# SCH_GasLeakIntegratedVer3_2026-06-25.net
KiCad netlist of a schematic drawn in EasyEDA
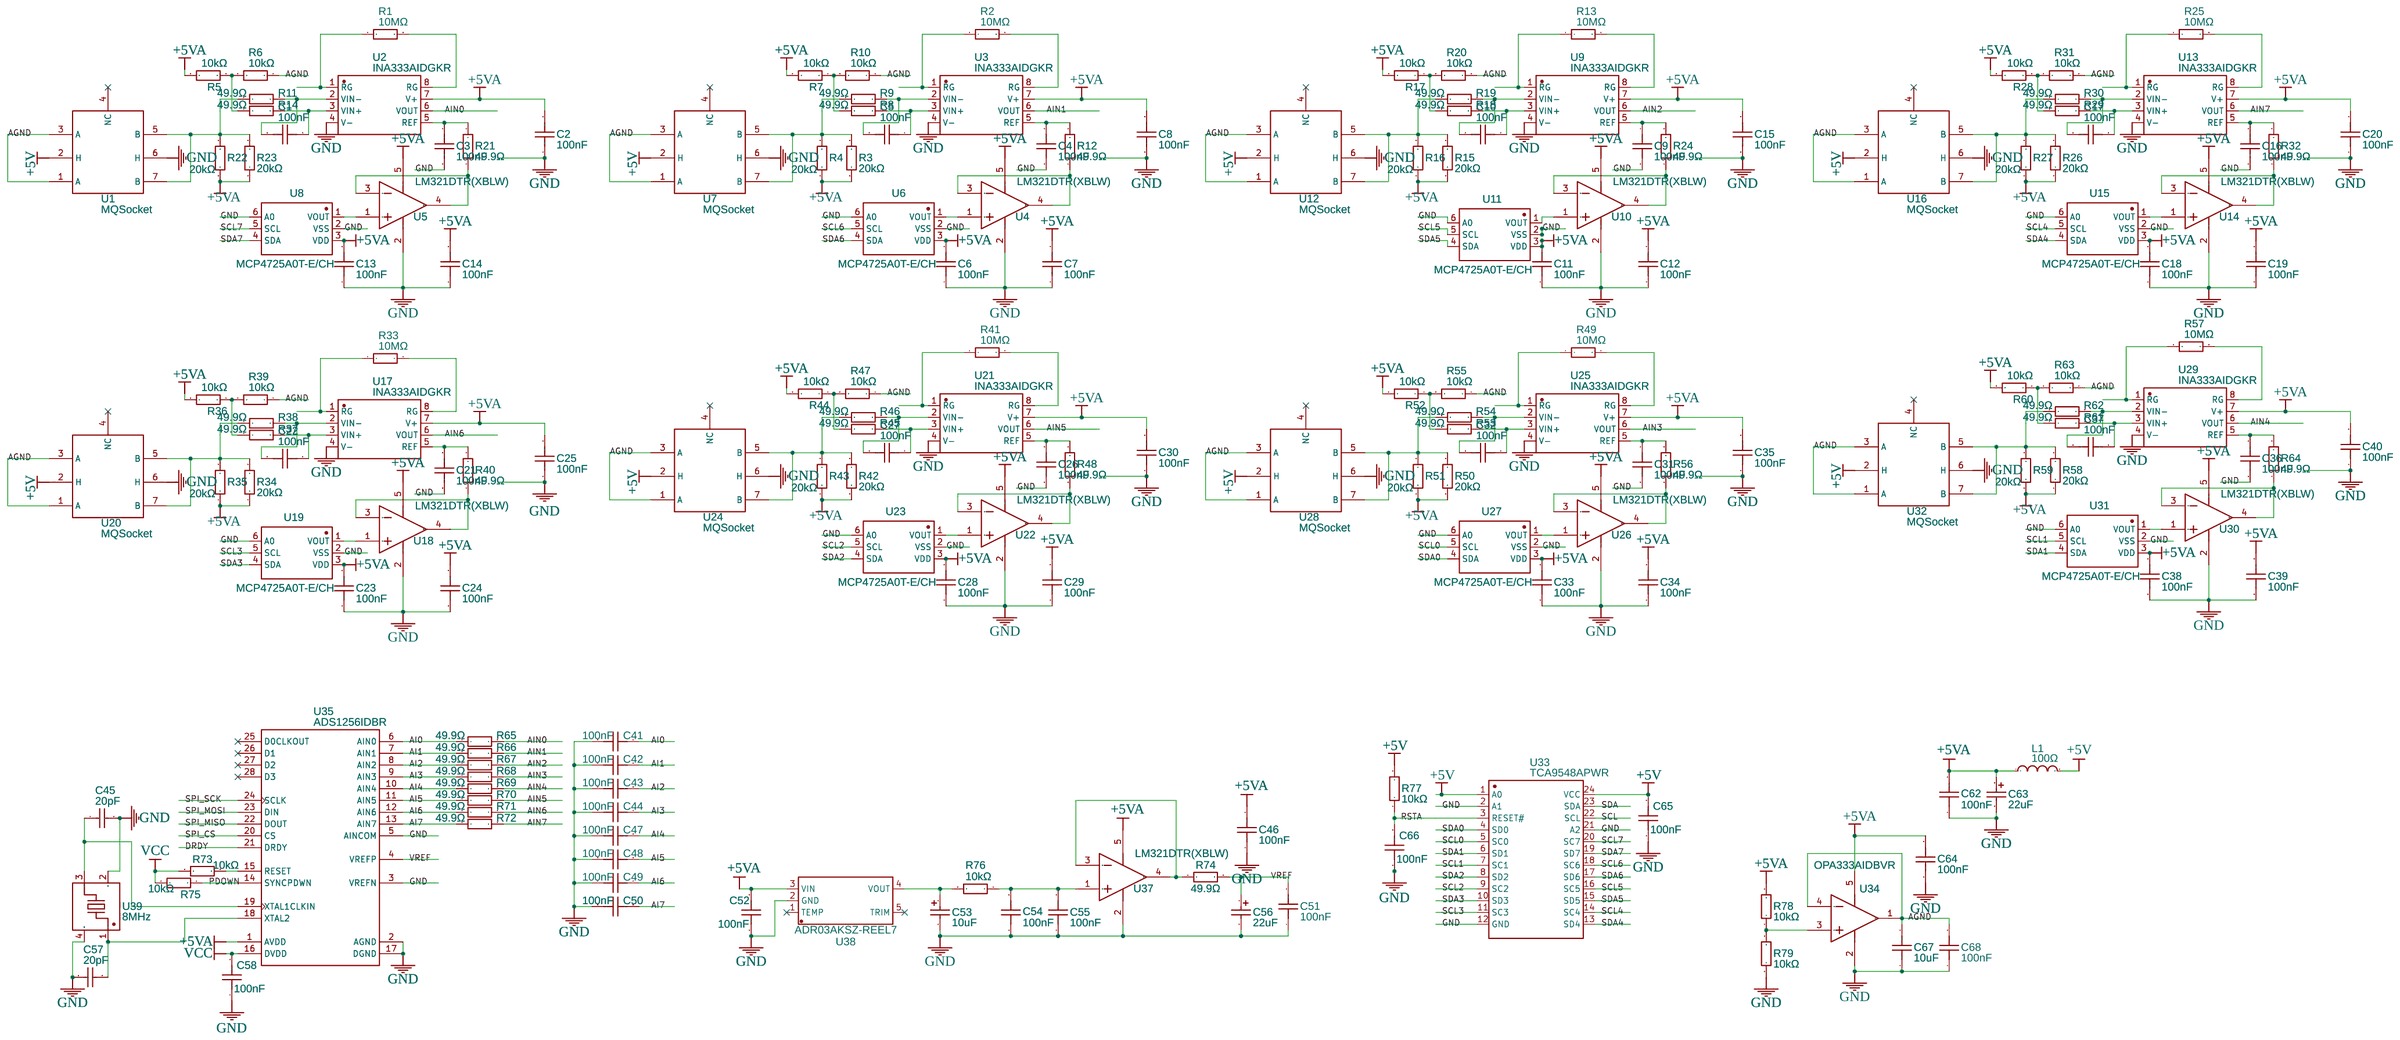
[diagram p0: Sheet_1]
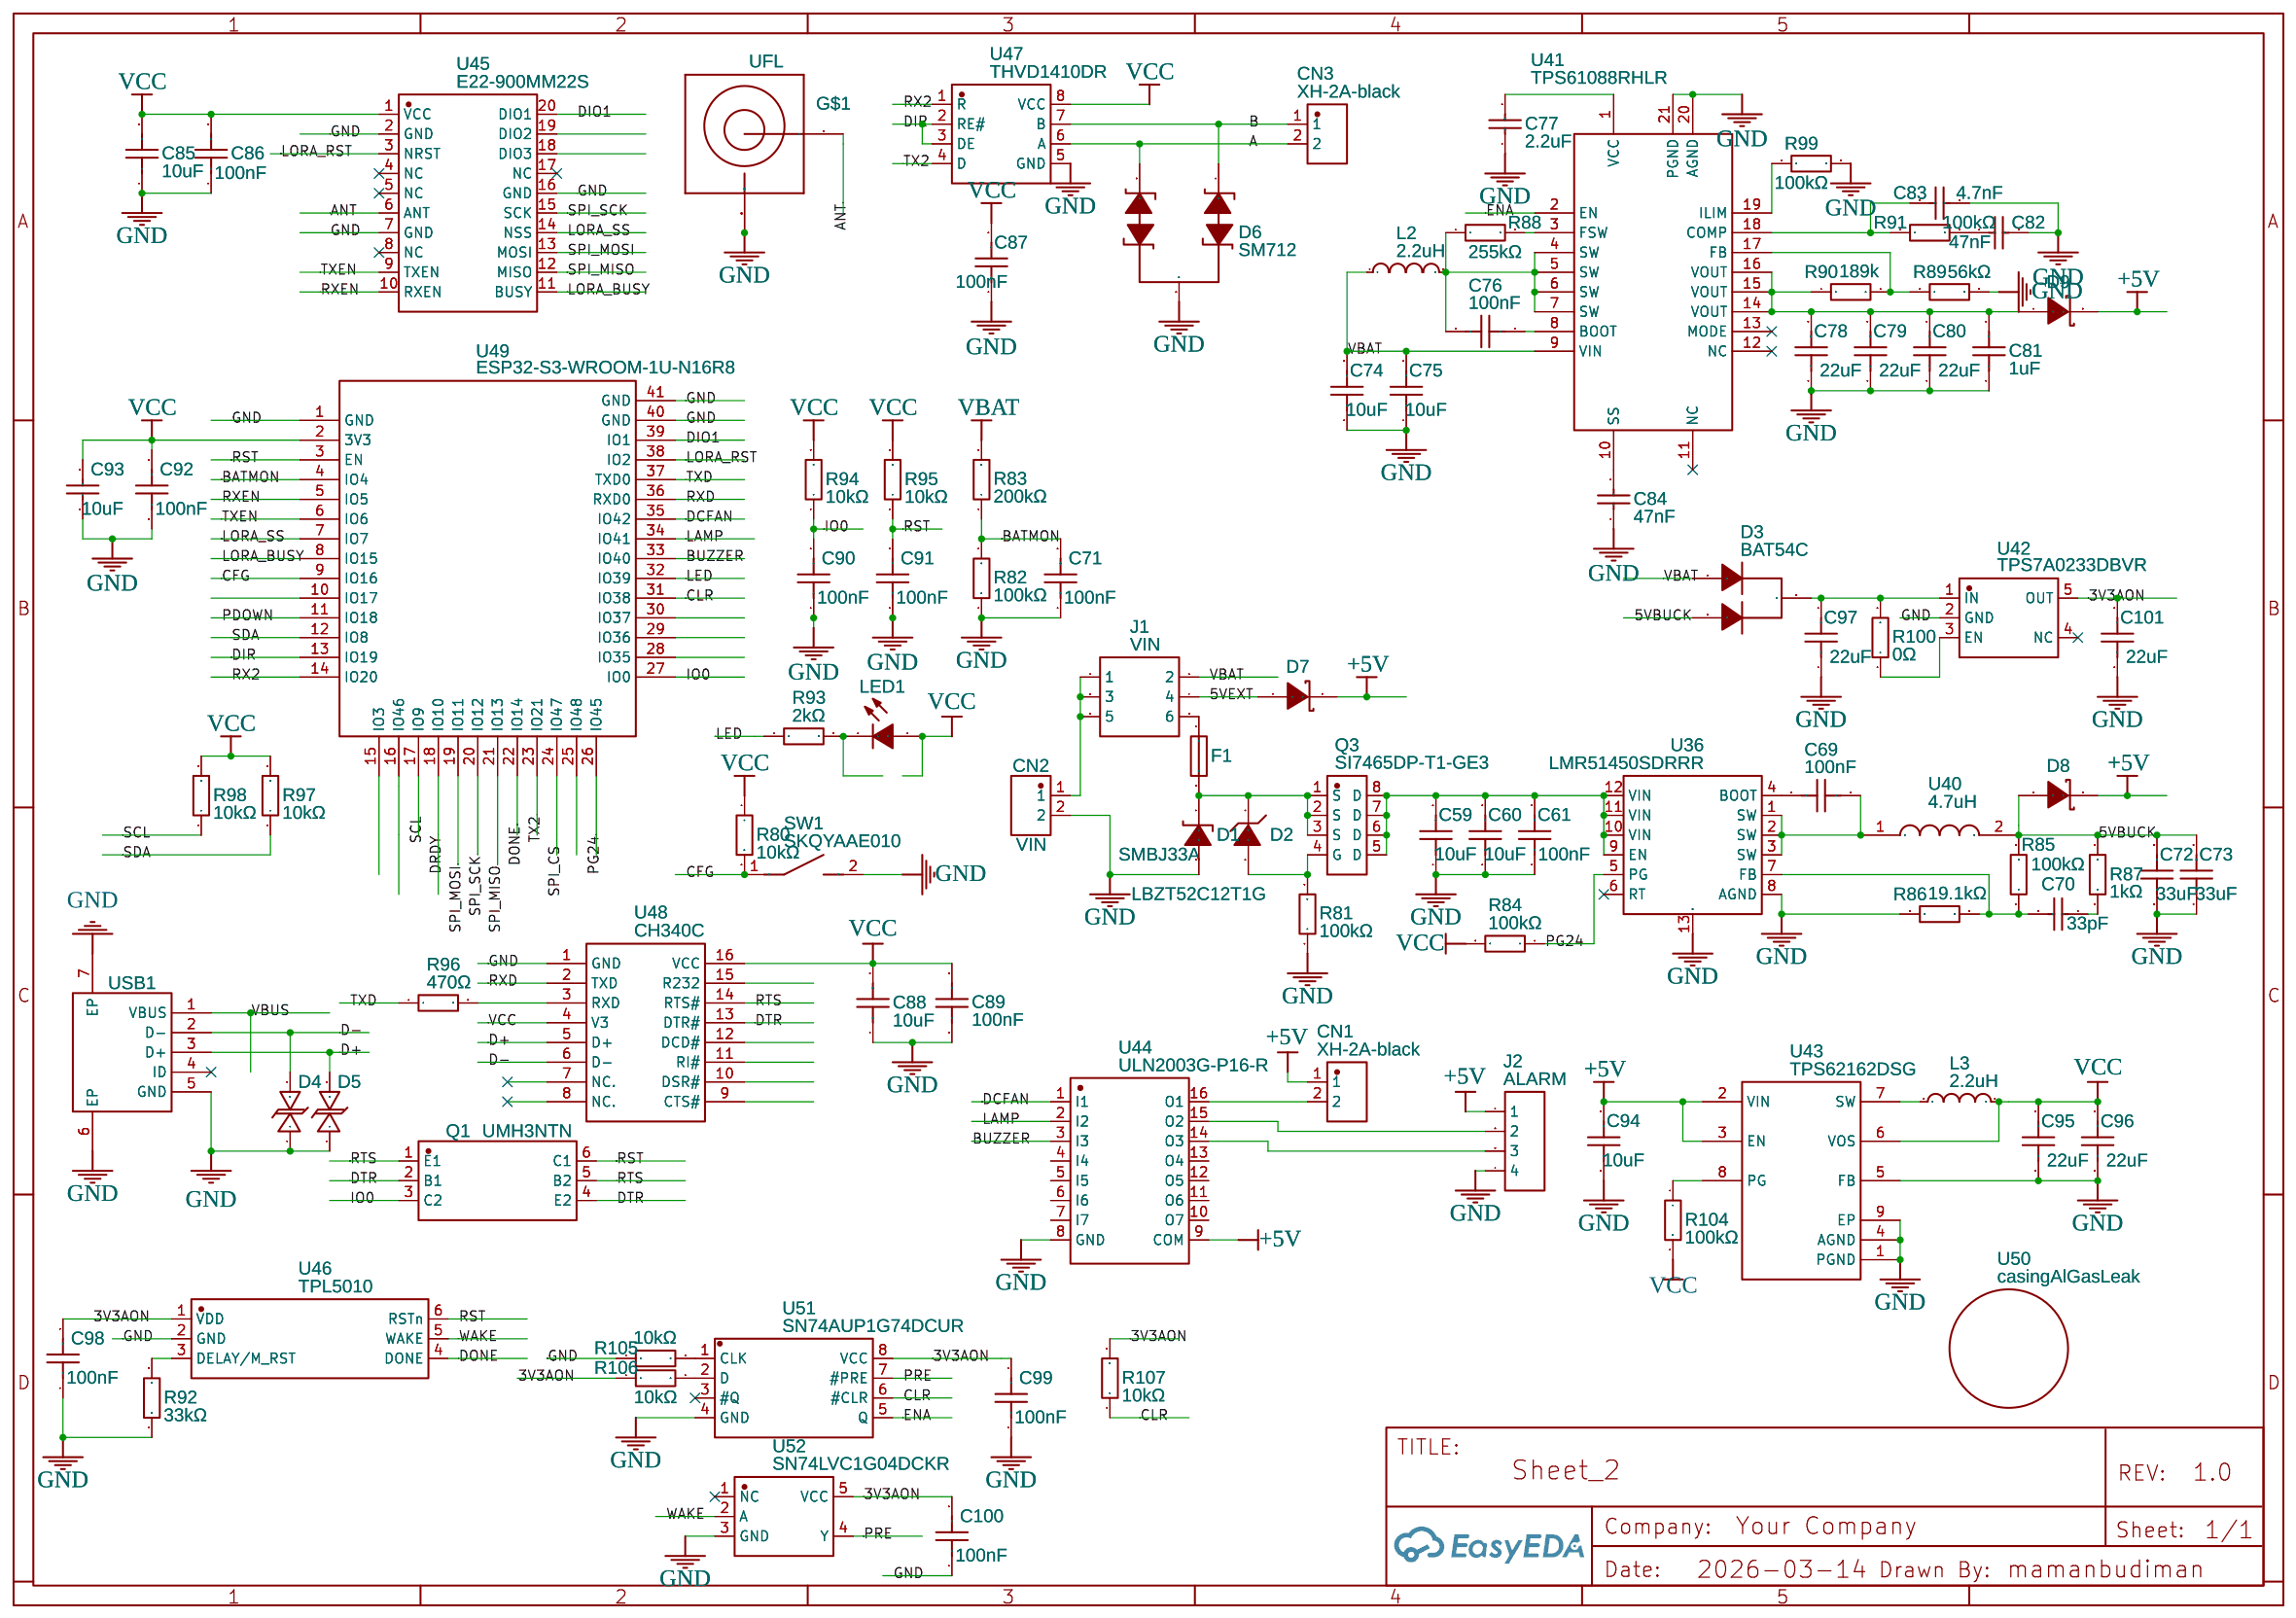
[diagram p1: Sheet_2]

(export (version "E")
  (design (tool "Eeschema 10.0.6"))
  (components
    (comp (ref "C1")
      (value "100nF")
      (fields
        (field (name "Manufacturer Part") "CL05B104KO5NNNC")
        (field (name "Manufacturer") "SAMSUNG(三星)")
      )
      (libsource (lib "") (part "CL05B104KO5NNNC_1"))
    )
    (comp (ref "C2")
      (value "100nF")
      (fields
        (field (name "Manufacturer Part") "CL05B104KO5NNNC")
        (field (name "Manufacturer") "SAMSUNG(三星)")
      )
      (libsource (lib "") (part "CL05B104KO5NNNC"))
    )
    (comp (ref "C3")
      (value "100nF")
      (fields
        (field (name "Manufacturer Part") "CL05B104KO5NNNC")
        (field (name "Manufacturer") "SAMSUNG(三星)")
      )
      (libsource (lib "") (part "CL05B104KO5NNNC_2"))
    )
    (comp (ref "C4")
      (value "100nF")
      (fields
        (field (name "Manufacturer Part") "CL05B104KO5NNNC")
        (field (name "Manufacturer") "SAMSUNG(三星)")
      )
      (libsource (lib "") (part "CL05B104KO5NNNC_2"))
    )
    (comp (ref "C5")
      (value "100nF")
      (fields
        (field (name "Manufacturer Part") "CL05B104KO5NNNC")
        (field (name "Manufacturer") "SAMSUNG(三星)")
      )
      (libsource (lib "") (part "CL05B104KO5NNNC_1"))
    )
    (comp (ref "C6")
      (value "100nF")
      (fields
        (field (name "Manufacturer Part") "CL05B104KO5NNNC")
        (field (name "Manufacturer") "SAMSUNG(三星)")
      )
      (libsource (lib "") (part "CL05B104KO5NNNC"))
    )
    (comp (ref "C7")
      (value "100nF")
      (fields
        (field (name "Manufacturer Part") "CL05B104KO5NNNC")
        (field (name "Manufacturer") "SAMSUNG(三星)")
      )
      (libsource (lib "") (part "CL05B104KO5NNNC"))
    )
    (comp (ref "C8")
      (value "100nF")
      (fields
        (field (name "Manufacturer Part") "CL05B104KO5NNNC")
        (field (name "Manufacturer") "SAMSUNG(三星)")
      )
      (libsource (lib "") (part "CL05B104KO5NNNC"))
    )
    (comp (ref "C9")
      (value "100nF")
      (fields
        (field (name "Manufacturer Part") "CL05B104KO5NNNC")
        (field (name "Manufacturer") "SAMSUNG(三星)")
      )
      (libsource (lib "") (part "CL05B104KO5NNNC_2"))
    )
    (comp (ref "C10")
      (value "100nF")
      (fields
        (field (name "Manufacturer Part") "CL05B104KO5NNNC")
        (field (name "Manufacturer") "SAMSUNG(三星)")
      )
      (libsource (lib "") (part "CL05B104KO5NNNC_1"))
    )
    (comp (ref "C11")
      (value "100nF")
      (fields
        (field (name "Manufacturer Part") "CL05B104KO5NNNC")
        (field (name "Manufacturer") "SAMSUNG(三星)")
      )
      (libsource (lib "") (part "CL05B104KO5NNNC"))
    )
    (comp (ref "C12")
      (value "100nF")
      (fields
        (field (name "Manufacturer Part") "CL05B104KO5NNNC")
        (field (name "Manufacturer") "SAMSUNG(三星)")
      )
      (libsource (lib "") (part "CL05B104KO5NNNC"))
    )
    (comp (ref "C13")
      (value "100nF")
      (fields
        (field (name "Manufacturer Part") "CL05B104KO5NNNC")
        (field (name "Manufacturer") "SAMSUNG(三星)")
      )
      (libsource (lib "") (part "CL05B104KO5NNNC"))
    )
    (comp (ref "C14")
      (value "100nF")
      (fields
        (field (name "Manufacturer Part") "CL05B104KO5NNNC")
        (field (name "Manufacturer") "SAMSUNG(三星)")
      )
      (libsource (lib "") (part "CL05B104KO5NNNC"))
    )
    (comp (ref "C15")
      (value "100nF")
      (fields
        (field (name "Manufacturer Part") "CL05B104KO5NNNC")
        (field (name "Manufacturer") "SAMSUNG(三星)")
      )
      (libsource (lib "") (part "CL05B104KO5NNNC"))
    )
    (comp (ref "C16")
      (value "100nF")
      (fields
        (field (name "Manufacturer Part") "CL05B104KO5NNNC")
        (field (name "Manufacturer") "SAMSUNG(三星)")
      )
      (libsource (lib "") (part "CL05B104KO5NNNC_2"))
    )
    (comp (ref "C17")
      (value "100nF")
      (fields
        (field (name "Manufacturer Part") "CL05B104KO5NNNC")
        (field (name "Manufacturer") "SAMSUNG(三星)")
      )
      (libsource (lib "") (part "CL05B104KO5NNNC_1"))
    )
    (comp (ref "C18")
      (value "100nF")
      (fields
        (field (name "Manufacturer Part") "CL05B104KO5NNNC")
        (field (name "Manufacturer") "SAMSUNG(三星)")
      )
      (libsource (lib "") (part "CL05B104KO5NNNC"))
    )
    (comp (ref "C19")
      (value "100nF")
      (fields
        (field (name "Manufacturer Part") "CL05B104KO5NNNC")
        (field (name "Manufacturer") "SAMSUNG(三星)")
      )
      (libsource (lib "") (part "CL05B104KO5NNNC"))
    )
    (comp (ref "C20")
      (value "100nF")
      (fields
        (field (name "Manufacturer Part") "CL05B104KO5NNNC")
        (field (name "Manufacturer") "SAMSUNG(三星)")
      )
      (libsource (lib "") (part "CL05B104KO5NNNC"))
    )
    (comp (ref "C21")
      (value "100nF")
      (fields
        (field (name "Manufacturer Part") "CL05B104KO5NNNC")
        (field (name "Manufacturer") "SAMSUNG(三星)")
      )
      (libsource (lib "") (part "CL05B104KO5NNNC_2"))
    )
    (comp (ref "C22")
      (value "100nF")
      (fields
        (field (name "Manufacturer Part") "CL05B104KO5NNNC")
        (field (name "Manufacturer") "SAMSUNG(三星)")
      )
      (libsource (lib "") (part "CL05B104KO5NNNC_1"))
    )
    (comp (ref "C23")
      (value "100nF")
      (fields
        (field (name "Manufacturer Part") "CL05B104KO5NNNC")
        (field (name "Manufacturer") "SAMSUNG(三星)")
      )
      (libsource (lib "") (part "CL05B104KO5NNNC"))
    )
    (comp (ref "C24")
      (value "100nF")
      (fields
        (field (name "Manufacturer Part") "CL05B104KO5NNNC")
        (field (name "Manufacturer") "SAMSUNG(三星)")
      )
      (libsource (lib "") (part "CL05B104KO5NNNC"))
    )
    (comp (ref "C25")
      (value "100nF")
      (fields
        (field (name "Manufacturer Part") "CL05B104KO5NNNC")
        (field (name "Manufacturer") "SAMSUNG(三星)")
      )
      (libsource (lib "") (part "CL05B104KO5NNNC"))
    )
    (comp (ref "C26")
      (value "100nF")
      (fields
        (field (name "Manufacturer Part") "CL05B104KO5NNNC")
        (field (name "Manufacturer") "SAMSUNG(三星)")
      )
      (libsource (lib "") (part "CL05B104KO5NNNC_2"))
    )
    (comp (ref "C27")
      (value "100nF")
      (fields
        (field (name "Manufacturer Part") "CL05B104KO5NNNC")
        (field (name "Manufacturer") "SAMSUNG(三星)")
      )
      (libsource (lib "") (part "CL05B104KO5NNNC_1"))
    )
    (comp (ref "C28")
      (value "100nF")
      (fields
        (field (name "Manufacturer Part") "CL05B104KO5NNNC")
        (field (name "Manufacturer") "SAMSUNG(三星)")
      )
      (libsource (lib "") (part "CL05B104KO5NNNC"))
    )
    (comp (ref "C29")
      (value "100nF")
      (fields
        (field (name "Manufacturer Part") "CL05B104KO5NNNC")
        (field (name "Manufacturer") "SAMSUNG(三星)")
      )
      (libsource (lib "") (part "CL05B104KO5NNNC"))
    )
    (comp (ref "C30")
      (value "100nF")
      (fields
        (field (name "Manufacturer Part") "CL05B104KO5NNNC")
        (field (name "Manufacturer") "SAMSUNG(三星)")
      )
      (libsource (lib "") (part "CL05B104KO5NNNC"))
    )
    (comp (ref "C31")
      (value "100nF")
      (fields
        (field (name "Manufacturer Part") "CL05B104KO5NNNC")
        (field (name "Manufacturer") "SAMSUNG(三星)")
      )
      (libsource (lib "") (part "CL05B104KO5NNNC_2"))
    )
    (comp (ref "C32")
      (value "100nF")
      (fields
        (field (name "Manufacturer Part") "CL05B104KO5NNNC")
        (field (name "Manufacturer") "SAMSUNG(三星)")
      )
      (libsource (lib "") (part "CL05B104KO5NNNC_1"))
    )
    (comp (ref "C33")
      (value "100nF")
      (fields
        (field (name "Manufacturer Part") "CL05B104KO5NNNC")
        (field (name "Manufacturer") "SAMSUNG(三星)")
      )
      (libsource (lib "") (part "CL05B104KO5NNNC"))
    )
    (comp (ref "C34")
      (value "100nF")
      (fields
        (field (name "Manufacturer Part") "CL05B104KO5NNNC")
        (field (name "Manufacturer") "SAMSUNG(三星)")
      )
      (libsource (lib "") (part "CL05B104KO5NNNC"))
    )
    (comp (ref "C35")
      (value "100nF")
      (fields
        (field (name "Manufacturer Part") "CL05B104KO5NNNC")
        (field (name "Manufacturer") "SAMSUNG(三星)")
      )
      (libsource (lib "") (part "CL05B104KO5NNNC"))
    )
    (comp (ref "C36")
      (value "100nF")
      (fields
        (field (name "Manufacturer Part") "CL05B104KO5NNNC")
        (field (name "Manufacturer") "SAMSUNG(三星)")
      )
      (libsource (lib "") (part "CL05B104KO5NNNC_2"))
    )
    (comp (ref "C37")
      (value "100nF")
      (fields
        (field (name "Manufacturer Part") "CL05B104KO5NNNC")
        (field (name "Manufacturer") "SAMSUNG(三星)")
      )
      (libsource (lib "") (part "CL05B104KO5NNNC_1"))
    )
    (comp (ref "C38")
      (value "100nF")
      (fields
        (field (name "Manufacturer Part") "CL05B104KO5NNNC")
        (field (name "Manufacturer") "SAMSUNG(三星)")
      )
      (libsource (lib "") (part "CL05B104KO5NNNC"))
    )
    (comp (ref "C39")
      (value "100nF")
      (fields
        (field (name "Manufacturer Part") "CL05B104KO5NNNC")
        (field (name "Manufacturer") "SAMSUNG(三星)")
      )
      (libsource (lib "") (part "CL05B104KO5NNNC"))
    )
    (comp (ref "C40")
      (value "100nF")
      (fields
        (field (name "Manufacturer Part") "CL05B104KO5NNNC")
        (field (name "Manufacturer") "SAMSUNG(三星)")
      )
      (libsource (lib "") (part "CL05B104KO5NNNC"))
    )
    (comp (ref "C41")
      (value "100nF")
      (fields
        (field (name "Manufacturer Part") "CL05B104KO5NNNC")
        (field (name "Manufacturer") "SAMSUNG(三星)")
      )
      (libsource (lib "") (part "CL05B104KO5NNNC_3"))
    )
    (comp (ref "C42")
      (value "100nF")
      (fields
        (field (name "Manufacturer Part") "CL05B104KO5NNNC")
        (field (name "Manufacturer") "SAMSUNG(三星)")
      )
      (libsource (lib "") (part "CL05B104KO5NNNC_3"))
    )
    (comp (ref "C43")
      (value "100nF")
      (fields
        (field (name "Manufacturer Part") "CL05B104KO5NNNC")
        (field (name "Manufacturer") "SAMSUNG(三星)")
      )
      (libsource (lib "") (part "CL05B104KO5NNNC_3"))
    )
    (comp (ref "C44")
      (value "100nF")
      (fields
        (field (name "Manufacturer Part") "CL05B104KO5NNNC")
        (field (name "Manufacturer") "SAMSUNG(三星)")
      )
      (libsource (lib "") (part "CL05B104KO5NNNC_3"))
    )
    (comp (ref "C45")
      (value "20pF")
      (fields (field (name "Manufacturer Part") "0402CG200J500NT") (field (name "Manufacturer") "FH(风华)"))
      (libsource (lib "") (part "0402CG200J500NT"))
    )
    (comp (ref "C46")
      (value "100nF")
      (fields
        (field (name "Manufacturer Part") "CL05B104KO5NNNC")
        (field (name "Manufacturer") "SAMSUNG(三星)")
      )
      (libsource (lib "") (part "CL05B104KO5NNNC"))
    )
    (comp (ref "C47")
      (value "100nF")
      (fields
        (field (name "Manufacturer Part") "CL05B104KO5NNNC")
        (field (name "Manufacturer") "SAMSUNG(三星)")
      )
      (libsource (lib "") (part "CL05B104KO5NNNC_3"))
    )
    (comp (ref "C48")
      (value "100nF")
      (fields
        (field (name "Manufacturer Part") "CL05B104KO5NNNC")
        (field (name "Manufacturer") "SAMSUNG(三星)")
      )
      (libsource (lib "") (part "CL05B104KO5NNNC_3"))
    )
    (comp (ref "C49")
      (value "100nF")
      (fields
        (field (name "Manufacturer Part") "CL05B104KO5NNNC")
        (field (name "Manufacturer") "SAMSUNG(三星)")
      )
      (libsource (lib "") (part "CL05B104KO5NNNC_3"))
    )
    (comp (ref "C50")
      (value "100nF")
      (fields
        (field (name "Manufacturer Part") "CL05B104KO5NNNC")
        (field (name "Manufacturer") "SAMSUNG(三星)")
      )
      (libsource (lib "") (part "CL05B104KO5NNNC_3"))
    )
    (comp (ref "C51")
      (value "100nF")
      (fields
        (field (name "Manufacturer Part") "CL05B104KO5NNNC")
        (field (name "Manufacturer") "SAMSUNG(三星)")
      )
      (libsource (lib "") (part "CL05B104KO5NNNC"))
    )
    (comp (ref "C52")
      (value "100nF")
      (fields
        (field (name "Manufacturer Part") "CL05B104KO5NNNC")
        (field (name "Manufacturer") "SAMSUNG(三星)")
      )
      (libsource (lib "") (part "CL05B104KO5NNNC"))
    )
    (comp (ref "C53")
      (value "10uF")
      (fields (field (name "Manufacturer Part") "TAJA106K016RNJ") (field (name "Manufacturer") "Kyocera AVX"))
      (libsource (lib "") (part "TAJA106K016RNJ"))
    )
    (comp (ref "C54")
      (value "100nF")
      (fields
        (field (name "Manufacturer Part") "CL05B104KO5NNNC")
        (field (name "Manufacturer") "SAMSUNG(三星)")
      )
      (libsource (lib "") (part "CL05B104KO5NNNC"))
    )
    (comp (ref "C55")
      (value "100nF")
      (fields
        (field (name "Manufacturer Part") "CL05B104KO5NNNC")
        (field (name "Manufacturer") "SAMSUNG(三星)")
      )
      (libsource (lib "") (part "CL05B104KO5NNNC"))
    )
    (comp (ref "C56")
      (value "22uF")
      (fields (field (name "Manufacturer Part") "TAJA226M010RNJ") (field (name "Manufacturer") "Kyocera AVX"))
      (libsource (lib "") (part "TAJA226M010RNJ"))
    )
    (comp (ref "C57")
      (value "20pF")
      (fields (field (name "Manufacturer Part") "0402CG200J500NT") (field (name "Manufacturer") "FH(风华)"))
      (libsource (lib "") (part "0402CG200J500NT"))
    )
    (comp (ref "C58")
      (value "100nF")
      (fields (field (name "Manufacturer Part") "CC0603KRX7R9BB104") (field (name "Manufacturer") "YAGEO"))
      (libsource (lib "") (part "CC0603KRX7R9BB104"))
    )
    (comp (ref "C62")
      (value "100nF")
      (fields
        (field (name "Manufacturer Part") "CL05B104KO5NNNC")
        (field (name "Manufacturer") "SAMSUNG(三星)")
      )
      (libsource (lib "") (part "CL05B104KO5NNNC"))
    )
    (comp (ref "C63")
      (value "22uF")
      (fields (field (name "Manufacturer Part") "TAJA226M010RNJ") (field (name "Manufacturer") "Kyocera AVX"))
      (libsource (lib "") (part "TAJA226M010RNJ"))
    )
    (comp (ref "C64")
      (value "100nF")
      (fields
        (field (name "Manufacturer Part") "CC0603KRX7R9BB104")
        (field (name "Manufacturer") "YAGEO(国巨)")
      )
      (libsource (lib "") (part "CC0603KRX7R9BB104"))
    )
    (comp (ref "C65")
      (value "100nF")
      (fields (field (name "Manufacturer Part") "CC0603KRX7R9BB104") (field (name "Manufacturer") "YAGEO"))
      (libsource (lib "") (part "CC0603KRX7R9BB104"))
    )
    (comp (ref "C66")
      (value "100nF")
      (fields (field (name "Manufacturer Part") "CC0603KRX7R9BB104") (field (name "Manufacturer") "YAGEO"))
      (libsource (lib "") (part "CC0603KRX7R9BB104"))
    )
    (comp (ref "C67")
      (value "10uF")
      (fields
        (field (name "Manufacturer Part") "CL10A106KP8NNNC")
        (field (name "Manufacturer") "SAMSUNG(三星)")
      )
      (libsource (lib "") (part "CL10A106KP8NNNC"))
    )
    (comp (ref "C68")
      (value "100nF")
      (fields
        (field (name "Manufacturer Part") "CC0603KRX7R9BB104")
        (field (name "Manufacturer") "YAGEO(国巨)")
      )
      (libsource (lib "") (part "CC0603KRX7R9BB104"))
    )
    (comp (ref "L1")
      (value "100Ω")
      (fields (field (name "Manufacturer Part") "GZ2012D101TF") (field (name "Manufacturer") "Sunlord(顺络)"))
      (libsource (lib "") (part "GZ2012D101TF"))
    )
    (comp (ref "R1")
      (value "10MΩ")
      (fields
        (field (name "Manufacturer Part") "0603WAF1005T5E")
        (field (name "Manufacturer") "UNI-ROYAL(厚声)")
      )
      (libsource (lib "") (part "0603WAF1005T5E"))
    )
    (comp (ref "R2")
      (value "10MΩ")
      (fields
        (field (name "Manufacturer Part") "0603WAF1005T5E")
        (field (name "Manufacturer") "UNI-ROYAL(厚声)")
      )
      (libsource (lib "") (part "0603WAF1005T5E"))
    )
    (comp (ref "R3")
      (value "20kΩ")
      (fields
        (field (name "Manufacturer Part") "0603WAF2002T5E")
        (field (name "Manufacturer") "UNI-ROYAL(厚声)")
      )
      (libsource (lib "") (part "0603WAF2002T5E"))
    )
    (comp (ref "R4")
      (value "20kΩ")
      (fields
        (field (name "Manufacturer Part") "0603WAF2002T5E")
        (field (name "Manufacturer") "UNI-ROYAL(厚声)")
      )
      (libsource (lib "") (part "0603WAF2002T5E"))
    )
    (comp (ref "R5")
      (value "10kΩ")
      (fields (field (name "Manufacturer Part") "RT0603BRD0710KL") (field (name "Manufacturer") "YAGEO(国巨)"))
      (libsource (lib "") (part "RT0603BRD0710KL"))
    )
    (comp (ref "R6")
      (value "10kΩ")
      (fields (field (name "Manufacturer Part") "RT0603BRD0710KL") (field (name "Manufacturer") "YAGEO(国巨)"))
      (libsource (lib "") (part "RT0603BRD0710KL"))
    )
    (comp (ref "R7")
      (value "10kΩ")
      (fields (field (name "Manufacturer Part") "RT0603BRD0710KL") (field (name "Manufacturer") "YAGEO(国巨)"))
      (libsource (lib "") (part "RT0603BRD0710KL"))
    )
    (comp (ref "R8")
      (value "49.9Ω")
      (fields (field (name "Manufacturer Part") "RC-02K49R9FT") (field (name "Manufacturer") "FH(风华)"))
      (libsource (lib "") (part "RC-02K49R9FT"))
    )
    (comp (ref "R9")
      (value "49.9Ω")
      (fields (field (name "Manufacturer Part") "RC-02K49R9FT") (field (name "Manufacturer") "FH(风华)"))
      (libsource (lib "") (part "RC-02K49R9FT"))
    )
    (comp (ref "R10")
      (value "10kΩ")
      (fields (field (name "Manufacturer Part") "RT0603BRD0710KL") (field (name "Manufacturer") "YAGEO(国巨)"))
      (libsource (lib "") (part "RT0603BRD0710KL"))
    )
    (comp (ref "R11")
      (value "49.9Ω")
      (fields (field (name "Manufacturer Part") "RC-02K49R9FT") (field (name "Manufacturer") "FH(风华)"))
      (libsource (lib "") (part "RC-02K49R9FT"))
    )
    (comp (ref "R12")
      (value "49.9Ω")
      (fields (field (name "Manufacturer Part") "RC-02K49R9FT") (field (name "Manufacturer") "FH(风华)"))
      (libsource (lib "") (part "RC-02K49R9FT_1"))
    )
    (comp (ref "R13")
      (value "10MΩ")
      (fields
        (field (name "Manufacturer Part") "0603WAF1005T5E")
        (field (name "Manufacturer") "UNI-ROYAL(厚声)")
      )
      (libsource (lib "") (part "0603WAF1005T5E"))
    )
    (comp (ref "R14")
      (value "49.9Ω")
      (fields (field (name "Manufacturer Part") "RC-02K49R9FT") (field (name "Manufacturer") "FH(风华)"))
      (libsource (lib "") (part "RC-02K49R9FT"))
    )
    (comp (ref "R15")
      (value "20kΩ")
      (fields
        (field (name "Manufacturer Part") "0603WAF2002T5E")
        (field (name "Manufacturer") "UNI-ROYAL(厚声)")
      )
      (libsource (lib "") (part "0603WAF2002T5E"))
    )
    (comp (ref "R16")
      (value "20kΩ")
      (fields
        (field (name "Manufacturer Part") "0603WAF2002T5E")
        (field (name "Manufacturer") "UNI-ROYAL(厚声)")
      )
      (libsource (lib "") (part "0603WAF2002T5E"))
    )
    (comp (ref "R17")
      (value "10kΩ")
      (fields (field (name "Manufacturer Part") "RT0603BRD0710KL") (field (name "Manufacturer") "YAGEO(国巨)"))
      (libsource (lib "") (part "RT0603BRD0710KL"))
    )
    (comp (ref "R18")
      (value "49.9Ω")
      (fields (field (name "Manufacturer Part") "RC-02K49R9FT") (field (name "Manufacturer") "FH(风华)"))
      (libsource (lib "") (part "RC-02K49R9FT"))
    )
    (comp (ref "R19")
      (value "49.9Ω")
      (fields (field (name "Manufacturer Part") "RC-02K49R9FT") (field (name "Manufacturer") "FH(风华)"))
      (libsource (lib "") (part "RC-02K49R9FT"))
    )
    (comp (ref "R20")
      (value "10kΩ")
      (fields (field (name "Manufacturer Part") "RT0603BRD0710KL") (field (name "Manufacturer") "YAGEO(国巨)"))
      (libsource (lib "") (part "RT0603BRD0710KL"))
    )
    (comp (ref "R21")
      (value "49.9Ω")
      (fields (field (name "Manufacturer Part") "RC-02K49R9FT") (field (name "Manufacturer") "FH(风华)"))
      (libsource (lib "") (part "RC-02K49R9FT_1"))
    )
    (comp (ref "R22")
      (value "20kΩ")
      (fields
        (field (name "Manufacturer Part") "0603WAF2002T5E")
        (field (name "Manufacturer") "UNI-ROYAL(厚声)")
      )
      (libsource (lib "") (part "0603WAF2002T5E"))
    )
    (comp (ref "R23")
      (value "20kΩ")
      (fields
        (field (name "Manufacturer Part") "0603WAF2002T5E")
        (field (name "Manufacturer") "UNI-ROYAL(厚声)")
      )
      (libsource (lib "") (part "0603WAF2002T5E"))
    )
    (comp (ref "R24")
      (value "49.9Ω")
      (fields (field (name "Manufacturer Part") "RC-02K49R9FT") (field (name "Manufacturer") "FH(风华)"))
      (libsource (lib "") (part "RC-02K49R9FT_1"))
    )
    (comp (ref "R25")
      (value "10MΩ")
      (fields
        (field (name "Manufacturer Part") "0603WAF1005T5E")
        (field (name "Manufacturer") "UNI-ROYAL(厚声)")
      )
      (libsource (lib "") (part "0603WAF1005T5E"))
    )
    (comp (ref "R26")
      (value "20kΩ")
      (fields
        (field (name "Manufacturer Part") "0603WAF2002T5E")
        (field (name "Manufacturer") "UNI-ROYAL(厚声)")
      )
      (libsource (lib "") (part "0603WAF2002T5E"))
    )
    (comp (ref "R27")
      (value "20kΩ")
      (fields
        (field (name "Manufacturer Part") "0603WAF2002T5E")
        (field (name "Manufacturer") "UNI-ROYAL(厚声)")
      )
      (libsource (lib "") (part "0603WAF2002T5E"))
    )
    (comp (ref "R28")
      (value "10kΩ")
      (fields (field (name "Manufacturer Part") "RT0603BRD0710KL") (field (name "Manufacturer") "YAGEO(国巨)"))
      (libsource (lib "") (part "RT0603BRD0710KL"))
    )
    (comp (ref "R29")
      (value "49.9Ω")
      (fields (field (name "Manufacturer Part") "RC-02K49R9FT") (field (name "Manufacturer") "FH(风华)"))
      (libsource (lib "") (part "RC-02K49R9FT"))
    )
    (comp (ref "R30")
      (value "49.9Ω")
      (fields (field (name "Manufacturer Part") "RC-02K49R9FT") (field (name "Manufacturer") "FH(风华)"))
      (libsource (lib "") (part "RC-02K49R9FT"))
    )
    (comp (ref "R31")
      (value "10kΩ")
      (fields (field (name "Manufacturer Part") "RT0603BRD0710KL") (field (name "Manufacturer") "YAGEO(国巨)"))
      (libsource (lib "") (part "RT0603BRD0710KL"))
    )
    (comp (ref "R32")
      (value "49.9Ω")
      (fields (field (name "Manufacturer Part") "RC-02K49R9FT") (field (name "Manufacturer") "FH(风华)"))
      (libsource (lib "") (part "RC-02K49R9FT_1"))
    )
    (comp (ref "R33")
      (value "10MΩ")
      (fields
        (field (name "Manufacturer Part") "0603WAF1005T5E")
        (field (name "Manufacturer") "UNI-ROYAL(厚声)")
      )
      (libsource (lib "") (part "0603WAF1005T5E"))
    )
    (comp (ref "R34")
      (value "20kΩ")
      (fields
        (field (name "Manufacturer Part") "0603WAF2002T5E")
        (field (name "Manufacturer") "UNI-ROYAL(厚声)")
      )
      (libsource (lib "") (part "0603WAF2002T5E"))
    )
    (comp (ref "R35")
      (value "20kΩ")
      (fields
        (field (name "Manufacturer Part") "0603WAF2002T5E")
        (field (name "Manufacturer") "UNI-ROYAL(厚声)")
      )
      (libsource (lib "") (part "0603WAF2002T5E"))
    )
    (comp (ref "R36")
      (value "10kΩ")
      (fields (field (name "Manufacturer Part") "RT0603BRD0710KL") (field (name "Manufacturer") "YAGEO(国巨)"))
      (libsource (lib "") (part "RT0603BRD0710KL"))
    )
    (comp (ref "R37")
      (value "49.9Ω")
      (fields (field (name "Manufacturer Part") "RC-02K49R9FT") (field (name "Manufacturer") "FH(风华)"))
      (libsource (lib "") (part "RC-02K49R9FT"))
    )
    (comp (ref "R38")
      (value "49.9Ω")
      (fields (field (name "Manufacturer Part") "RC-02K49R9FT") (field (name "Manufacturer") "FH(风华)"))
      (libsource (lib "") (part "RC-02K49R9FT"))
    )
    (comp (ref "R39")
      (value "10kΩ")
      (fields (field (name "Manufacturer Part") "RT0603BRD0710KL") (field (name "Manufacturer") "YAGEO(国巨)"))
      (libsource (lib "") (part "RT0603BRD0710KL"))
    )
    (comp (ref "R40")
      (value "49.9Ω")
      (fields (field (name "Manufacturer Part") "RC-02K49R9FT") (field (name "Manufacturer") "FH(风华)"))
      (libsource (lib "") (part "RC-02K49R9FT_1"))
    )
    (comp (ref "R41")
      (value "10MΩ")
      (fields
        (field (name "Manufacturer Part") "0603WAF1005T5E")
        (field (name "Manufacturer") "UNI-ROYAL(厚声)")
      )
      (libsource (lib "") (part "0603WAF1005T5E"))
    )
    (comp (ref "R42")
      (value "20kΩ")
      (fields
        (field (name "Manufacturer Part") "0603WAF2002T5E")
        (field (name "Manufacturer") "UNI-ROYAL(厚声)")
      )
      (libsource (lib "") (part "0603WAF2002T5E"))
    )
    (comp (ref "R43")
      (value "20kΩ")
      (fields
        (field (name "Manufacturer Part") "0603WAF2002T5E")
        (field (name "Manufacturer") "UNI-ROYAL(厚声)")
      )
      (libsource (lib "") (part "0603WAF2002T5E"))
    )
    (comp (ref "R44")
      (value "10kΩ")
      (fields (field (name "Manufacturer Part") "RT0603BRD0710KL") (field (name "Manufacturer") "YAGEO(国巨)"))
      (libsource (lib "") (part "RT0603BRD0710KL"))
    )
    (comp (ref "R45")
      (value "49.9Ω")
      (fields (field (name "Manufacturer Part") "RC-02K49R9FT") (field (name "Manufacturer") "FH(风华)"))
      (libsource (lib "") (part "RC-02K49R9FT"))
    )
    (comp (ref "R46")
      (value "49.9Ω")
      (fields (field (name "Manufacturer Part") "RC-02K49R9FT") (field (name "Manufacturer") "FH(风华)"))
      (libsource (lib "") (part "RC-02K49R9FT"))
    )
    (comp (ref "R47")
      (value "10kΩ")
      (fields (field (name "Manufacturer Part") "RT0603BRD0710KL") (field (name "Manufacturer") "YAGEO(国巨)"))
      (libsource (lib "") (part "RT0603BRD0710KL"))
    )
    (comp (ref "R48")
      (value "49.9Ω")
      (fields (field (name "Manufacturer Part") "RC-02K49R9FT") (field (name "Manufacturer") "FH(风华)"))
      (libsource (lib "") (part "RC-02K49R9FT_1"))
    )
    (comp (ref "R49")
      (value "10MΩ")
      (fields
        (field (name "Manufacturer Part") "0603WAF1005T5E")
        (field (name "Manufacturer") "UNI-ROYAL(厚声)")
      )
      (libsource (lib "") (part "0603WAF1005T5E"))
    )
    (comp (ref "R50")
      (value "20kΩ")
      (fields
        (field (name "Manufacturer Part") "0603WAF2002T5E")
        (field (name "Manufacturer") "UNI-ROYAL(厚声)")
      )
      (libsource (lib "") (part "0603WAF2002T5E"))
    )
    (comp (ref "R51")
      (value "20kΩ")
      (fields
        (field (name "Manufacturer Part") "0603WAF2002T5E")
        (field (name "Manufacturer") "UNI-ROYAL(厚声)")
      )
      (libsource (lib "") (part "0603WAF2002T5E"))
    )
    (comp (ref "R52")
      (value "10kΩ")
      (fields (field (name "Manufacturer Part") "RT0603BRD0710KL") (field (name "Manufacturer") "YAGEO(国巨)"))
      (libsource (lib "") (part "RT0603BRD0710KL"))
    )
    (comp (ref "R53")
      (value "49.9Ω")
      (fields (field (name "Manufacturer Part") "RC-02K49R9FT") (field (name "Manufacturer") "FH(风华)"))
      (libsource (lib "") (part "RC-02K49R9FT"))
    )
    (comp (ref "R54")
      (value "49.9Ω")
      (fields (field (name "Manufacturer Part") "RC-02K49R9FT") (field (name "Manufacturer") "FH(风华)"))
      (libsource (lib "") (part "RC-02K49R9FT"))
    )
    (comp (ref "R55")
      (value "10kΩ")
      (fields (field (name "Manufacturer Part") "RT0603BRD0710KL") (field (name "Manufacturer") "YAGEO(国巨)"))
      (libsource (lib "") (part "RT0603BRD0710KL"))
    )
    (comp (ref "R56")
      (value "49.9Ω")
      (fields (field (name "Manufacturer Part") "RC-02K49R9FT") (field (name "Manufacturer") "FH(风华)"))
      (libsource (lib "") (part "RC-02K49R9FT_1"))
    )
    (comp (ref "R57")
      (value "10MΩ")
      (fields
        (field (name "Manufacturer Part") "0603WAF1005T5E")
        (field (name "Manufacturer") "UNI-ROYAL(厚声)")
      )
      (libsource (lib "") (part "0603WAF1005T5E"))
    )
    (comp (ref "R58")
      (value "20kΩ")
      (fields
        (field (name "Manufacturer Part") "0603WAF2002T5E")
        (field (name "Manufacturer") "UNI-ROYAL(厚声)")
      )
      (libsource (lib "") (part "0603WAF2002T5E"))
    )
    (comp (ref "R59")
      (value "20kΩ")
      (fields
        (field (name "Manufacturer Part") "0603WAF2002T5E")
        (field (name "Manufacturer") "UNI-ROYAL(厚声)")
      )
      (libsource (lib "") (part "0603WAF2002T5E"))
    )
    (comp (ref "R60")
      (value "10kΩ")
      (fields (field (name "Manufacturer Part") "RT0603BRD0710KL") (field (name "Manufacturer") "YAGEO(国巨)"))
      (libsource (lib "") (part "RT0603BRD0710KL"))
    )
    (comp (ref "R61")
      (value "49.9Ω")
      (fields (field (name "Manufacturer Part") "RC-02K49R9FT") (field (name "Manufacturer") "FH(风华)"))
      (libsource (lib "") (part "RC-02K49R9FT"))
    )
    (comp (ref "R62")
      (value "49.9Ω")
      (fields (field (name "Manufacturer Part") "RC-02K49R9FT") (field (name "Manufacturer") "FH(风华)"))
      (libsource (lib "") (part "RC-02K49R9FT"))
    )
    (comp (ref "R63")
      (value "10kΩ")
      (fields (field (name "Manufacturer Part") "RT0603BRD0710KL") (field (name "Manufacturer") "YAGEO(国巨)"))
      (libsource (lib "") (part "RT0603BRD0710KL"))
    )
    (comp (ref "R64")
      (value "49.9Ω")
      (fields (field (name "Manufacturer Part") "RC-02K49R9FT") (field (name "Manufacturer") "FH(风华)"))
      (libsource (lib "") (part "RC-02K49R9FT_1"))
    )
    (comp (ref "R65")
      (value "49.9Ω")
      (fields (field (name "Manufacturer Part") "RC-02K49R9FT") (field (name "Manufacturer") "FH(风华)"))
      (libsource (lib "") (part "RC-02K49R9FT"))
    )
    (comp (ref "R66")
      (value "49.9Ω")
      (fields (field (name "Manufacturer Part") "RC-02K49R9FT") (field (name "Manufacturer") "FH(风华)"))
      (libsource (lib "") (part "RC-02K49R9FT"))
    )
    (comp (ref "R67")
      (value "49.9Ω")
      (fields (field (name "Manufacturer Part") "RC-02K49R9FT") (field (name "Manufacturer") "FH(风华)"))
      (libsource (lib "") (part "RC-02K49R9FT"))
    )
    (comp (ref "R68")
      (value "49.9Ω")
      (fields (field (name "Manufacturer Part") "RC-02K49R9FT") (field (name "Manufacturer") "FH(风华)"))
      (libsource (lib "") (part "RC-02K49R9FT"))
    )
    (comp (ref "R69")
      (value "49.9Ω")
      (fields (field (name "Manufacturer Part") "RC-02K49R9FT") (field (name "Manufacturer") "FH(风华)"))
      (libsource (lib "") (part "RC-02K49R9FT"))
    )
    (comp (ref "R70")
      (value "49.9Ω")
      (fields (field (name "Manufacturer Part") "RC-02K49R9FT") (field (name "Manufacturer") "FH(风华)"))
      (libsource (lib "") (part "RC-02K49R9FT"))
    )
    (comp (ref "R71")
      (value "49.9Ω")
      (fields (field (name "Manufacturer Part") "RC-02K49R9FT") (field (name "Manufacturer") "FH(风华)"))
      (libsource (lib "") (part "RC-02K49R9FT"))
    )
    (comp (ref "R72")
      (value "49.9Ω")
      (fields (field (name "Manufacturer Part") "RC-02K49R9FT") (field (name "Manufacturer") "FH(风华)"))
      (libsource (lib "") (part "RC-02K49R9FT"))
    )
    (comp (ref "R73")
      (value "10kΩ")
      (fields (field (name "Manufacturer Part") "RT0603BRD0710KL") (field (name "Manufacturer") "YAGEO(国巨)"))
      (libsource (lib "") (part "RT0603BRD0710KL"))
    )
    (comp (ref "R74")
      (value "49.9Ω")
      (fields (field (name "Manufacturer Part") "RC-02K49R9FT") (field (name "Manufacturer") "FH(风华)"))
      (libsource (lib "") (part "RC-02K49R9FT"))
    )
    (comp (ref "R75")
      (value "10kΩ")
      (fields (field (name "Manufacturer Part") "RT0603BRD0710KL") (field (name "Manufacturer") "YAGEO(国巨)"))
      (libsource (lib "") (part "RT0603BRD0710KL"))
    )
    (comp (ref "R76")
      (value "10kΩ")
      (fields (field (name "Manufacturer Part") "RT0603BRD0710KL") (field (name "Manufacturer") "YAGEO(国巨)"))
      (libsource (lib "") (part "RT0603BRD0710KL"))
    )
    (comp (ref "R77")
      (value "10kΩ")
      (fields (field (name "Manufacturer Part") "0603WAF1002T5E") (field (name "Manufacturer") "UniOhm"))
      (libsource (lib "") (part "0603WAF1002T5E"))
    )
    (comp (ref "R78")
      (value "10kΩ")
      (fields (field (name "Manufacturer Part") "RT0603BRD0710KL") (field (name "Manufacturer") "YAGEO(国巨)"))
      (libsource (lib "") (part "RT0603BRD0710KL_1"))
    )
    (comp (ref "R79")
      (value "10kΩ")
      (fields (field (name "Manufacturer Part") "RT0603BRD0710KL") (field (name "Manufacturer") "YAGEO(国巨)"))
      (libsource (lib "") (part "RT0603BRD0710KL_1"))
    )
    (comp (ref "U1") (value "MQSocket") (libsource (lib "") (part "MQSocket")))
    (comp (ref "U2")
      (value "INA333AIDGKR")
      (fields (field (name "Manufacturer") "TI(德州仪器)"))
      (libsource (lib "") (part "INA333AIDGKR"))
    )
    (comp (ref "U3")
      (value "INA333AIDGKR")
      (fields (field (name "Manufacturer") "TI(德州仪器)"))
      (libsource (lib "") (part "INA333AIDGKR"))
    )
    (comp (ref "U4")
      (value "LM321DTR(XBLW)")
      (fields (field (name "Manufacturer") "XBLW(芯伯乐)"))
      (libsource (lib "") (part "LM321DTR(XBLW)"))
    )
    (comp (ref "U5")
      (value "LM321DTR(XBLW)")
      (fields (field (name "Manufacturer") "XBLW(芯伯乐)"))
      (libsource (lib "") (part "LM321DTR(XBLW)"))
    )
    (comp (ref "U6")
      (value "MCP4725A0T-E/CH")
      (fields (field (name "Manufacturer") "MICROCHIP(美国微芯)"))
      (libsource (lib "") (part "MCP4725A0T-E/CH"))
    )
    (comp (ref "U7") (value "MQSocket") (libsource (lib "") (part "MQSocket")))
    (comp (ref "U8")
      (value "MCP4725A0T-E/CH")
      (fields (field (name "Manufacturer") "MICROCHIP(美国微芯)"))
      (libsource (lib "") (part "MCP4725A0T-E/CH"))
    )
    (comp (ref "U9")
      (value "INA333AIDGKR")
      (fields (field (name "Manufacturer") "TI(德州仪器)"))
      (libsource (lib "") (part "INA333AIDGKR"))
    )
    (comp (ref "U10")
      (value "LM321DTR(XBLW)")
      (fields (field (name "Manufacturer") "XBLW(芯伯乐)"))
      (libsource (lib "") (part "LM321DTR(XBLW)"))
    )
    (comp (ref "U11")
      (value "MCP4725A0T-E/CH")
      (fields (field (name "Manufacturer") "MICROCHIP(美国微芯)"))
      (libsource (lib "") (part "MCP4725A0T-E/CH"))
    )
    (comp (ref "U12") (value "MQSocket") (libsource (lib "") (part "MQSocket")))
    (comp (ref "U13")
      (value "INA333AIDGKR")
      (fields (field (name "Manufacturer") "TI(德州仪器)"))
      (libsource (lib "") (part "INA333AIDGKR"))
    )
    (comp (ref "U14")
      (value "LM321DTR(XBLW)")
      (fields (field (name "Manufacturer") "XBLW(芯伯乐)"))
      (libsource (lib "") (part "LM321DTR(XBLW)"))
    )
    (comp (ref "U15")
      (value "MCP4725A0T-E/CH")
      (fields (field (name "Manufacturer") "MICROCHIP(美国微芯)"))
      (libsource (lib "") (part "MCP4725A0T-E/CH"))
    )
    (comp (ref "U16") (value "MQSocket") (libsource (lib "") (part "MQSocket")))
    (comp (ref "U17")
      (value "INA333AIDGKR")
      (fields (field (name "Manufacturer") "TI(德州仪器)"))
      (libsource (lib "") (part "INA333AIDGKR"))
    )
    (comp (ref "U18")
      (value "LM321DTR(XBLW)")
      (fields (field (name "Manufacturer") "XBLW(芯伯乐)"))
      (libsource (lib "") (part "LM321DTR(XBLW)"))
    )
    (comp (ref "U19")
      (value "MCP4725A0T-E/CH")
      (fields (field (name "Manufacturer") "MICROCHIP(美国微芯)"))
      (libsource (lib "") (part "MCP4725A0T-E/CH"))
    )
    (comp (ref "U20") (value "MQSocket") (libsource (lib "") (part "MQSocket")))
    (comp (ref "U21")
      (value "INA333AIDGKR")
      (fields (field (name "Manufacturer") "TI(德州仪器)"))
      (libsource (lib "") (part "INA333AIDGKR"))
    )
    (comp (ref "U22")
      (value "LM321DTR(XBLW)")
      (fields (field (name "Manufacturer") "XBLW(芯伯乐)"))
      (libsource (lib "") (part "LM321DTR(XBLW)"))
    )
    (comp (ref "U23")
      (value "MCP4725A0T-E/CH")
      (fields (field (name "Manufacturer") "MICROCHIP(美国微芯)"))
      (libsource (lib "") (part "MCP4725A0T-E/CH"))
    )
    (comp (ref "U24") (value "MQSocket") (libsource (lib "") (part "MQSocket")))
    (comp (ref "U25")
      (value "INA333AIDGKR")
      (fields (field (name "Manufacturer") "TI(德州仪器)"))
      (libsource (lib "") (part "INA333AIDGKR"))
    )
    (comp (ref "U26")
      (value "LM321DTR(XBLW)")
      (fields (field (name "Manufacturer") "XBLW(芯伯乐)"))
      (libsource (lib "") (part "LM321DTR(XBLW)"))
    )
    (comp (ref "U27")
      (value "MCP4725A0T-E/CH")
      (fields (field (name "Manufacturer") "MICROCHIP(美国微芯)"))
      (libsource (lib "") (part "MCP4725A0T-E/CH"))
    )
    (comp (ref "U28") (value "MQSocket") (libsource (lib "") (part "MQSocket")))
    (comp (ref "U29")
      (value "INA333AIDGKR")
      (fields (field (name "Manufacturer") "TI(德州仪器)"))
      (libsource (lib "") (part "INA333AIDGKR"))
    )
    (comp (ref "U30")
      (value "LM321DTR(XBLW)")
      (fields (field (name "Manufacturer") "XBLW(芯伯乐)"))
      (libsource (lib "") (part "LM321DTR(XBLW)"))
    )
    (comp (ref "U31")
      (value "MCP4725A0T-E/CH")
      (fields (field (name "Manufacturer") "MICROCHIP(美国微芯)"))
      (libsource (lib "") (part "MCP4725A0T-E/CH"))
    )
    (comp (ref "U32") (value "MQSocket") (libsource (lib "") (part "MQSocket")))
    (comp (ref "U33")
      (value "TCA9548APWR")
      (fields (field (name "Manufacturer") "TI(德州仪器)"))
      (libsource (lib "") (part "TCA9548APWR"))
    )
    (comp (ref "U34")
      (value "OPA333AIDBVR")
      (fields (field (name "Manufacturer") "TI(德州仪器)"))
      (libsource (lib "") (part "OPA333AIDBVR"))
    )
    (comp (ref "U35")
      (value "ADS1256IDBR")
      (fields (field (name "Manufacturer") "TI(德州仪器)"))
      (libsource (lib "") (part "ADS1256IDBR"))
    )
    (comp (ref "U37")
      (value "LM321DTR(XBLW)")
      (fields (field (name "Manufacturer") "XBLW(芯伯乐)"))
      (libsource (lib "") (part "LM321DTR(XBLW)"))
    )
    (comp (ref "U38")
      (value "ADR03AKSZ-REEL7")
      (fields (field (name "Manufacturer") "ADI(亚德诺)"))
      (libsource (lib "") (part "ADR03AKSZ-REEL7"))
    )
    (comp (ref "U39")
      (value "8MHz")
      (fields (field (name "Manufacturer Part") "3TJ480000NYLBC") (field (name "Manufacturer") "JYJE(晶友嘉)"))
      (libsource (lib "") (part "3TJ480000NYLBC"))
    )
    (comp (ref "C59")
      (value "10uF")
      (fields
        (field (name "Manufacturer Part") "GRM21BR61H106KE43L")
        (field (name "Manufacturer") "muRata(村田)")
      )
      (libsource (lib "") (part "GRM21BR61H106KE43L"))
    )
    (comp (ref "C60")
      (value "10uF")
      (fields
        (field (name "Manufacturer Part") "GRM21BR61H106KE43L")
        (field (name "Manufacturer") "muRata(村田)")
      )
      (libsource (lib "") (part "GRM21BR61H106KE43L"))
    )
    (comp (ref "C61")
      (value "100nF")
      (fields (field (name "Manufacturer Part") "CC0603KRX7R9BB104") (field (name "Manufacturer") "YAGEO"))
      (libsource (lib "") (part "CC0603KRX7R9BB104"))
    )
    (comp (ref "C69")
      (value "100nF")
      (fields (field (name "Manufacturer Part") "CC0603KRX7R9BB104") (field (name "Manufacturer") "YAGEO"))
      (libsource (lib "") (part "CC0603KRX7R9BB104_1"))
    )
    (comp (ref "C70")
      (value "33pF")
      (fields
        (field (name "Manufacturer Part") "CL10C330JB8NNNC")
        (field (name "Manufacturer") "SAMSUNG(三星)")
      )
      (libsource (lib "") (part "CL10C330JB8NNNC"))
    )
    (comp (ref "C71")
      (value "100nF")
      (fields (field (name "Manufacturer Part") "CC0603KRX7R9BB104") (field (name "Manufacturer") "YAGEO"))
      (libsource (lib "") (part "CC0603KRX7R9BB104"))
    )
    (comp (ref "C72")
      (value "33uF")
      (fields (field (name "Manufacturer Part") "C2012X5R1A336MTJ00E") (field (name "Manufacturer") "TDK"))
      (libsource (lib "") (part "C2012X5R1A336MTJ00E"))
    )
    (comp (ref "C73")
      (value "33uF")
      (fields (field (name "Manufacturer Part") "C2012X5R1A336MTJ00E") (field (name "Manufacturer") "TDK"))
      (libsource (lib "") (part "C2012X5R1A336MTJ00E"))
    )
    (comp (ref "C74")
      (value "10uF")
      (fields
        (field (name "Manufacturer Part") "GRM21BR61H106KE43L")
        (field (name "Manufacturer") "muRata(村田)")
      )
      (libsource (lib "") (part "GRM21BR61H106KE43L"))
    )
    (comp (ref "C75")
      (value "10uF")
      (fields
        (field (name "Manufacturer Part") "GRM21BR61H106KE43L")
        (field (name "Manufacturer") "muRata(村田)")
      )
      (libsource (lib "") (part "GRM21BR61H106KE43L"))
    )
    (comp (ref "C76")
      (value "100nF")
      (fields (field (name "Manufacturer Part") "CC0603KRX7R9BB104") (field (name "Manufacturer") "YAGEO"))
      (libsource (lib "") (part "CC0603KRX7R9BB104_1"))
    )
    (comp (ref "C77")
      (value "2.2uF")
      (fields
        (field (name "Manufacturer Part") "CL10A225KO8NNNC")
        (field (name "Manufacturer") "SAMSUNG(三星)")
      )
      (libsource (lib "") (part "CL10A225KO8NNNC"))
    )
    (comp (ref "C78")
      (value "22uF")
      (fields
        (field (name "Manufacturer Part") "CL10A226MQ8NRNC")
        (field (name "Manufacturer") "SAMSUNG(三星)")
      )
      (libsource (lib "") (part "CL10A226MQ8NRNC"))
    )
    (comp (ref "C79")
      (value "22uF")
      (fields
        (field (name "Manufacturer Part") "CL10A226MQ8NRNC")
        (field (name "Manufacturer") "SAMSUNG(三星)")
      )
      (libsource (lib "") (part "CL10A226MQ8NRNC"))
    )
    (comp (ref "C80")
      (value "22uF")
      (fields
        (field (name "Manufacturer Part") "CL10A226MQ8NRNC")
        (field (name "Manufacturer") "SAMSUNG(三星)")
      )
      (libsource (lib "") (part "CL10A226MQ8NRNC"))
    )
    (comp (ref "C81")
      (value "1uF")
      (fields
        (field (name "Manufacturer Part") "CL10A105KB8NNNC")
        (field (name "Manufacturer") "SAMSUNG(三星)")
      )
      (libsource (lib "") (part "CL10A105KB8NNNC"))
    )
    (comp (ref "C82")
      (value "47nF")
      (fields
        (field (name "Manufacturer Part") "CL10B473KB8NNNC")
        (field (name "Manufacturer") "SAMSUNG(三星)")
      )
      (libsource (lib "") (part "CL10B473KB8NNNC_1"))
    )
    (comp (ref "C83")
      (value "4.7nF")
      (fields (field (name "Manufacturer Part") "0603B472K500NT") (field (name "Manufacturer") "FH(风华)"))
      (libsource (lib "") (part "0603B472K500NT"))
    )
    (comp (ref "C84")
      (value "47nF")
      (fields
        (field (name "Manufacturer Part") "CL10B473KB8NNNC")
        (field (name "Manufacturer") "SAMSUNG(三星)")
      )
      (libsource (lib "") (part "CL10B473KB8NNNC"))
    )
    (comp (ref "C85")
      (value "10uF")
      (fields (field (name "Manufacturer Part") "CL10A106KP8NNNC") (field (name "Manufacturer") "SAMSUNG"))
      (libsource (lib "") (part "CL10A106KP8NNNC"))
    )
    (comp (ref "C86")
      (value "100nF")
      (fields
        (field (name "Manufacturer Part") "CC0603KRX7R9BB104")
        (field (name "Manufacturer") "YAGEO(国巨)")
      )
      (libsource (lib "") (part "CC0603KRX7R9BB104"))
    )
    (comp (ref "C87")
      (value "100nF")
      (fields
        (field (name "Manufacturer Part") "CL05B104KO5NNNC")
        (field (name "Manufacturer") "SAMSUNG(三星)")
      )
      (libsource (lib "") (part "CL05B104KO5NNNC"))
    )
    (comp (ref "C88")
      (value "10uF")
      (fields
        (field (name "Manufacturer Part") "CL10A106KP8NNNC")
        (field (name "Manufacturer") "SAMSUNG(三星)")
      )
      (libsource (lib "") (part "CL10A106KP8NNNC"))
    )
    (comp (ref "C89")
      (value "100nF")
      (fields
        (field (name "Manufacturer Part") "CC0603KRX7R9BB104")
        (field (name "Manufacturer") "YAGEO(国巨)")
      )
      (libsource (lib "") (part "CC0603KRX7R9BB104"))
    )
    (comp (ref "C90")
      (value "100nF")
      (fields (field (name "Manufacturer Part") "CC0603KRX7R9BB104") (field (name "Manufacturer") "YAGEO"))
      (libsource (lib "") (part "CC0603KRX7R9BB104"))
    )
    (comp (ref "C91")
      (value "100nF")
      (fields (field (name "Manufacturer Part") "CC0603KRX7R9BB104") (field (name "Manufacturer") "YAGEO"))
      (libsource (lib "") (part "CC0603KRX7R9BB104"))
    )
    (comp (ref "C92")
      (value "100nF")
      (fields (field (name "Manufacturer Part") "CC0603KRX7R9BB104") (field (name "Manufacturer") "YAGEO"))
      (libsource (lib "") (part "CC0603KRX7R9BB104"))
    )
    (comp (ref "C93")
      (value "10uF")
      (fields (field (name "Manufacturer Part") "CL31A106KBHNNNE") (field (name "Manufacturer") "SAMSUNG"))
      (libsource (lib "") (part "CL31A106KBHNNNE"))
    )
    (comp (ref "C94")
      (value "10uF")
      (fields
        (field (name "Manufacturer Part") "GRM21BR61H106KE43L")
        (field (name "Manufacturer") "muRata(村田)")
      )
      (libsource (lib "") (part "GRM21BR61H106KE43L"))
    )
    (comp (ref "C95")
      (value "22uF")
      (fields
        (field (name "Manufacturer Part") "CL10A226MQ8NRNC")
        (field (name "Manufacturer") "SAMSUNG(三星)")
      )
      (libsource (lib "") (part "CL10A226MQ8NRNC"))
    )
    (comp (ref "C96")
      (value "22uF")
      (fields
        (field (name "Manufacturer Part") "CL10A226MQ8NRNC")
        (field (name "Manufacturer") "SAMSUNG(三星)")
      )
      (libsource (lib "") (part "CL10A226MQ8NRNC"))
    )
    (comp (ref "C97")
      (value "22uF")
      (fields
        (field (name "Manufacturer Part") "CL10A226MQ8NRNC")
        (field (name "Manufacturer") "SAMSUNG(三星)")
      )
      (libsource (lib "") (part "CL10A226MQ8NRNC"))
    )
    (comp (ref "C98")
      (value "100nF")
      (fields (field (name "Manufacturer Part") "CC0603KRX7R9BB104") (field (name "Manufacturer") "YAGEO"))
      (libsource (lib "") (part "CC0603KRX7R9BB104"))
    )
    (comp (ref "C99")
      (value "100nF")
      (fields (field (name "Manufacturer Part") "CC0603KRX7R9BB104") (field (name "Manufacturer") "YAGEO"))
      (libsource (lib "") (part "CC0603KRX7R9BB104"))
    )
    (comp (ref "C100")
      (value "100nF")
      (fields (field (name "Manufacturer Part") "CC0603KRX7R9BB104") (field (name "Manufacturer") "YAGEO"))
      (libsource (lib "") (part "CC0603KRX7R9BB104"))
    )
    (comp (ref "C101")
      (value "22uF")
      (fields
        (field (name "Manufacturer Part") "CL10A226MQ8NRNC")
        (field (name "Manufacturer") "SAMSUNG(三星)")
      )
      (libsource (lib "") (part "CL10A226MQ8NRNC"))
    )
    (comp (ref "CN1")
      (value "XH-2A-black")
      (fields (field (name "Manufacturer Part") "XH-2A黑色") (field (name "Manufacturer") "BOOMELE(博穆精密)"))
      (libsource (lib "") (part "XH-2A-black_1"))
    )
    (comp (ref "CN2")
      (value "VIN")
      (fields (field (name "Manufacturer Part") "XH-2A黑色") (field (name "Manufacturer") "BOOMELE(博穆精密)"))
      (libsource (lib "") (part "XH-2A-black"))
    )
    (comp (ref "CN3")
      (value "XH-2A-black")
      (fields (field (name "Manufacturer Part") "XH-2A黑色") (field (name "Manufacturer") "BOOMELE(博穆精密)"))
      (libsource (lib "") (part "XH-2A-black_1"))
    )
    (comp (ref "D1")
      (value "SMBJ33A")
      (fields (field (name "Manufacturer") "RUILON(瑞隆源)"))
      (libsource (lib "") (part "SMBJ33A"))
    )
    (comp (ref "D2")
      (value "LBZT52C12T1G")
      (fields (field (name "Manufacturer") "LRC(乐山无线电)"))
      (libsource (lib "") (part "LBZT52C12T1G"))
    )
    (comp (ref "D3")
      (value "BAT54C")
      (fields (field (name "Manufacturer") "CJ(江苏长电/长晶)"))
      (libsource (lib "") (part "BAT54C"))
    )
    (comp (ref "D4")
      (value "LESD5D5.0CT1G_C5199850")
      (fields (field (name "Manufacturer Part") "LESD5D5.0CT1G") (field (name "Manufacturer") "UMW(友台半导体)"))
      (libsource (lib "") (part "LESD5D5.0CT1G_C5199850"))
    )
    (comp (ref "D5")
      (value "LESD5D5.0CT1G_C5199850")
      (fields (field (name "Manufacturer Part") "LESD5D5.0CT1G") (field (name "Manufacturer") "UMW(友台半导体)"))
      (libsource (lib "") (part "LESD5D5.0CT1G_C5199850"))
    )
    (comp (ref "D6")
      (value "SM712")
      (fields (field (name "Manufacturer") "DOWO(东沃)"))
      (libsource (lib "") (part "SM712_C293966"))
    )
    (comp (ref "D7")
      (value "SS54_C22452")
      (fields (field (name "Manufacturer Part") "SS54") (field (name "Manufacturer") "MDD(辰达半导体)"))
      (libsource (lib "") (part "SS54_C22452"))
    )
    (comp (ref "D8")
      (value "SS54_C22452")
      (fields (field (name "Manufacturer Part") "SS54") (field (name "Manufacturer") "MDD(辰达半导体)"))
      (libsource (lib "") (part "SS54_C22452"))
    )
    (comp (ref "D9")
      (value "SS54_C22452")
      (fields (field (name "Manufacturer Part") "SS54") (field (name "Manufacturer") "MDD(辰达半导体)"))
      (libsource (lib "") (part "SS54_C22452"))
    )
    (comp (ref "F1")
      (value "MINISMDC260F/16")
      (fields
        (field (name "Manufacturer Part") "MINISMDC260F/16-2")
        (field (name "Manufacturer") "Littelfuse(美国力特)")
      )
      (libsource (lib "") (part "MINISMDC260F/16"))
    )
    (comp (ref "G$1") (value "UFL") (libsource (lib "") (part "UFL")))
    (comp (ref "J1") (value "VIN") (libsource (lib "") (part "HDR-M-2.54_2x3")))
    (comp (ref "J2") (value "ALARM") (libsource (lib "") (part "HDR-M-2.54_1x4")))
    (comp (ref "L2")
      (value "2.2uH")
      (fields (field (name "Manufacturer Part") "SMDRH105R-2R2NT") (field (name "Manufacturer") "SXN(顺翔诺)"))
      (libsource (lib "") (part "SMDRH105R-2R2NT"))
    )
    (comp (ref "L3")
      (value "2.2uH")
      (fields (field (name "Manufacturer Part") "ANR3015T2R2M") (field (name "Manufacturer") "APV(爱普微)"))
      (libsource (lib "") (part "ANR3015T2R2M"))
    )
    (comp (ref "LED1")
      (value "19-217/BHC-ZL1M2RY/3T")
      (fields (field (name "Manufacturer") "EVERLIGHT"))
      (libsource (lib "") (part "19-217/BHC-ZL1M2RY/3T"))
    )
    (comp (ref "Q1")
      (value "UMH3NTN")
      (fields (field (name "Manufacturer") "ROHM(罗姆)"))
      (libsource (lib "") (part "UMH3NTN"))
    )
    (comp (ref "Q3")
      (value "SI7465DP-T1-GE3")
      (fields (field (name "Manufacturer") "VISHAY(威世)"))
      (libsource (lib "") (part "SI7465DP-T1-GE3"))
    )
    (comp (ref "R80")
      (value "10kΩ")
      (fields (field (name "Manufacturer Part") "0603WAF1002T5E") (field (name "Manufacturer") "UniOhm"))
      (libsource (lib "") (part "0603WAF1002T5E_2"))
    )
    (comp (ref "R81")
      (value "100kΩ")
      (fields
        (field (name "Manufacturer Part") "0603WAF1003T5E")
        (field (name "Manufacturer") "UNI-ROYAL(厚声)")
      )
      (libsource (lib "") (part "0603WAF1003T5E_1"))
    )
    (comp (ref "R82")
      (value "100kΩ")
      (fields
        (field (name "Manufacturer Part") "0603WAF1003T5E")
        (field (name "Manufacturer") "UNI-ROYAL(厚声)")
      )
      (libsource (lib "") (part "0603WAF1003T5E_1"))
    )
    (comp (ref "R83")
      (value "200kΩ")
      (fields
        (field (name "Manufacturer Part") "0603WAF2003T5E")
        (field (name "Manufacturer") "UNI-ROYAL(厚声)")
      )
      (libsource (lib "") (part "0603WAF2003T5E"))
    )
    (comp (ref "R84")
      (value "100kΩ")
      (fields
        (field (name "Manufacturer Part") "0603WAF1003T5E")
        (field (name "Manufacturer") "UNI-ROYAL(厚声)")
      )
      (libsource (lib "") (part "0603WAF1003T5E_3"))
    )
    (comp (ref "R85")
      (value "100kΩ")
      (fields
        (field (name "Manufacturer Part") "0603WAF1003T5E")
        (field (name "Manufacturer") "UNI-ROYAL(厚声)")
      )
      (libsource (lib "") (part "0603WAF1003T5E_1"))
    )
    (comp (ref "R86")
      (value "19.1kΩ")
      (fields
        (field (name "Manufacturer Part") "0603WAF1912T5E")
        (field (name "Manufacturer") "UNI-ROYAL(厚声)")
      )
      (libsource (lib "") (part "0603WAF1912T5E"))
    )
    (comp (ref "R87")
      (value "1kΩ")
      (fields
        (field (name "Manufacturer Part") "0603WAF1001T5E")
        (field (name "Manufacturer") "UNI-ROYAL(厚声)")
      )
      (libsource (lib "") (part "0603WAF1001T5E"))
    )
    (comp (ref "R88")
      (value "255kΩ")
      (fields
        (field (name "Manufacturer Part") "0603WAF2553T5E")
        (field (name "Manufacturer") "UNI-ROYAL(厚声)")
      )
      (libsource (lib "") (part "0603WAF2553T5E"))
    )
    (comp (ref "R89")
      (value "56kΩ")
      (fields
        (field (name "Manufacturer Part") "0603WAF5602T5E")
        (field (name "Manufacturer") "UNI-ROYAL(厚声)")
      )
      (libsource (lib "") (part "0603WAF5602T5E"))
    )
    (comp (ref "R90")
      (value "189k")
      (fields (field (name "Manufacturer Part") "RT0603BRD07189KL") (field (name "Manufacturer") "YAGEO(国巨)"))
      (libsource (lib "") (part "RT0603BRD07189KL"))
    )
    (comp (ref "R91")
      (value "100kΩ")
      (fields
        (field (name "Manufacturer Part") "0603WAF1003T5E")
        (field (name "Manufacturer") "UNI-ROYAL(厚声)")
      )
      (libsource (lib "") (part "0603WAF1003T5E"))
    )
    (comp (ref "R92")
      (value "33kΩ")
      (fields
        (field (name "Manufacturer Part") "0603WAF3302T5E")
        (field (name "Manufacturer") "UNI-ROYAL(厚声)")
      )
      (libsource (lib "") (part "0603WAF3302T5E"))
    )
    (comp (ref "R93")
      (value "2kΩ")
      (fields
        (field (name "Manufacturer Part") "0603WAF2001T5E")
        (field (name "Manufacturer") "UNI-ROYAL(厚声)")
      )
      (libsource (lib "") (part "0603WAF2001T5E"))
    )
    (comp (ref "R94")
      (value "10kΩ")
      (fields (field (name "Manufacturer Part") "0603WAF1002T5E") (field (name "Manufacturer") "UniOhm"))
      (libsource (lib "") (part "0603WAF1002T5E"))
    )
    (comp (ref "R95")
      (value "10kΩ")
      (fields (field (name "Manufacturer Part") "0603WAF1002T5E") (field (name "Manufacturer") "UniOhm"))
      (libsource (lib "") (part "0603WAF1002T5E"))
    )
    (comp (ref "R96")
      (value "470Ω")
      (fields
        (field (name "Manufacturer Part") "0603WAF4700T5E")
        (field (name "Manufacturer") "UNI-ROYAL(厚声)")
      )
      (libsource (lib "") (part "0603WAF4700T5E"))
    )
    (comp (ref "R97")
      (value "10kΩ")
      (fields (field (name "Manufacturer Part") "0603WAF1002T5E") (field (name "Manufacturer") "UniOhm"))
      (libsource (lib "") (part "0603WAF1002T5E"))
    )
    (comp (ref "R98")
      (value "10kΩ")
      (fields (field (name "Manufacturer Part") "0603WAF1002T5E") (field (name "Manufacturer") "UniOhm"))
      (libsource (lib "") (part "0603WAF1002T5E"))
    )
    (comp (ref "R99")
      (value "100kΩ")
      (fields
        (field (name "Manufacturer Part") "0603WAF1003T5E")
        (field (name "Manufacturer") "UNI-ROYAL(厚声)")
      )
      (libsource (lib "") (part "0603WAF1003T5E"))
    )
    (comp (ref "R100")
      (value "0Ω")
      (fields
        (field (name "Manufacturer Part") "0603WAF0000T5E")
        (field (name "Manufacturer") "UNI-ROYAL(厚声)")
      )
      (libsource (lib "") (part "0603WAF0000T5E"))
    )
    (comp (ref "R104")
      (value "100kΩ")
      (fields
        (field (name "Manufacturer Part") "0603WAF1003T5E")
        (field (name "Manufacturer") "UNI-ROYAL(厚声)")
      )
      (libsource (lib "") (part "0603WAF1003T5E_2"))
    )
    (comp (ref "R105")
      (value "10kΩ")
      (fields (field (name "Manufacturer Part") "0603WAF1002T5E") (field (name "Manufacturer") "UniOhm"))
      (libsource (lib "") (part "0603WAF1002T5E_1"))
    )
    (comp (ref "R106")
      (value "10kΩ")
      (fields (field (name "Manufacturer Part") "0603WAF1002T5E") (field (name "Manufacturer") "UniOhm"))
      (libsource (lib "") (part "0603WAF1002T5E_1"))
    )
    (comp (ref "R107")
      (value "10kΩ")
      (fields (field (name "Manufacturer Part") "0603WAF1002T5E") (field (name "Manufacturer") "UniOhm"))
      (libsource (lib "") (part "0603WAF1002T5E"))
    )
    (comp (ref "SW1")
      (value "SKQYAAE010")
      (fields (field (name "Manufacturer") "ALPSALPINE(阿尔卑斯阿尔派)"))
      (libsource (lib "") (part "SKQYAAE010"))
    )
    (comp (ref "U36")
      (value "LMR51450SDRRR")
      (fields (field (name "Manufacturer") "TI(德州仪器)"))
      (libsource (lib "") (part "LMR51450SDRRR"))
    )
    (comp (ref "U40")
      (value "4.7uH")
      (fields (field (name "Manufacturer Part") "GSSM06304R7M2AU") (field (name "Manufacturer") "ABC(千如)"))
      (libsource (lib "") (part "GSSM06304R7M2AU"))
    )
    (comp (ref "U41")
      (value "TPS61088RHLR")
      (fields (field (name "Manufacturer") "TI(德州仪器)"))
      (libsource (lib "") (part "TPS61088RHLR"))
    )
    (comp (ref "U42")
      (value "TPS7A0233DBVR")
      (fields (field (name "Manufacturer") "TI(德州仪器)"))
      (libsource (lib "") (part "TPS7A0233DBVR"))
    )
    (comp (ref "U43")
      (value "TPS62162DSG")
      (fields (field (name "Manufacturer Part") "TPS62162DSGR") (field (name "Manufacturer") "TI(德州仪器)"))
      (libsource (lib "") (part "TPS62162DSG"))
    )
    (comp (ref "U44")
      (value "ULN2003G-P16-R")
      (fields (field (name "Manufacturer") "UTC(友顺)"))
      (libsource (lib "") (part "ULN2003G-P16-R"))
    )
    (comp (ref "U45")
      (value "E22-900MM22S")
      (fields (field (name "Manufacturer") "EBYTE(亿佰特)"))
      (libsource (lib "") (part "E22-900MM22S"))
    )
    (comp (ref "U46")
      (value "TPL5010")
      (fields (field (name "Manufacturer Part") "TPL5010DDCR") (field (name "Manufacturer") "TI(德州仪器)"))
      (libsource (lib "") (part "TPL5010DDCR"))
    )
    (comp (ref "U47")
      (value "THVD1410DR")
      (fields (field (name "Manufacturer") "TI(德州仪器)"))
      (libsource (lib "") (part "THVD1410DR"))
    )
    (comp (ref "U48")
      (value "CH340C")
      (fields (field (name "Manufacturer") "WCH(南京沁恒)"))
      (libsource (lib "") (part "CH340C"))
    )
    (comp (ref "U49")
      (value "ESP32-S3-WROOM-1U-N16R8")
      (fields (field (name "Manufacturer") "ESPRESSIF(乐鑫)"))
      (libsource (lib "") (part "ESP32-S3-WROOM-1U-N16R8"))
    )
    (comp (ref "U50") (value "casingAlGasLeak") (libsource (lib "") (part "casingAlGasLeak")))
    (comp (ref "U51")
      (value "SN74AUP1G74DCUR")
      (fields (field (name "Manufacturer") "TI(德州仪器)"))
      (libsource (lib "") (part "SN74AUP1G74DCUR"))
    )
    (comp (ref "U52")
      (value "SN74LVC1G04DCKR")
      (fields (field (name "Manufacturer") "TI(德州仪器)"))
      (libsource (lib "") (part "SN74LVC1G04DCKR"))
    )
    (comp (ref "USB1")
      (value "U-D-M5DD-W-1")
      (fields (field (name "Manufacturer") "韩国韩荣"))
      (libsource (lib "") (part "U-D-M5DD-W-1"))
    )
  )
  (nets
    (net (code "1") (name "+5V") (class "Default")
      (node (ref "C65") (pin "2") (pinfunction "2_2") (pintype "unspecified"))
      (node (ref "C94") (pin "2") (pinfunction "2_2") (pintype "unspecified"))
      (node (ref "CN1") (pin "1") (pinfunction "1_1") (pintype "unspecified"))
      (node (ref "D7") (pin "2") (pinfunction "K_2") (pintype "unspecified"))
      (node (ref "D8") (pin "2") (pinfunction "K_2") (pintype "unspecified"))
      (node (ref "D9") (pin "2") (pinfunction "K_2") (pintype "unspecified"))
      (node (ref "J2") (pin "1") (pinfunction "1_1") (pintype "unspecified"))
      (node (ref "L1") (pin "2") (pinfunction "2_2") (pintype "unspecified"))
      (node (ref "R77") (pin "2") (pinfunction "2_2") (pintype "input"))
      (node (ref "U1") (pin "2") (pinfunction "H_2") (pintype "unspecified"))
      (node (ref "U12") (pin "2") (pinfunction "H_2") (pintype "unspecified"))
      (node (ref "U16") (pin "2") (pinfunction "H_2") (pintype "unspecified"))
      (node (ref "U20") (pin "2") (pinfunction "H_2") (pintype "unspecified"))
      (node (ref "U24") (pin "2") (pinfunction "H_2") (pintype "unspecified"))
      (node (ref "U28") (pin "2") (pinfunction "H_2") (pintype "unspecified"))
      (node (ref "U32") (pin "2") (pinfunction "H_2") (pintype "unspecified"))
      (node (ref "U33") (pin "1") (pinfunction "A0_1") (pintype "unspecified"))
      (node (ref "U33") (pin "24") (pinfunction "VCC_24") (pintype "unspecified"))
      (node (ref "U43") (pin "2") (pinfunction "VIN_2") (pintype "passive"))
      (node (ref "U43") (pin "3") (pinfunction "EN_3") (pintype "unspecified"))
      (node (ref "U44") (pin "9") (pinfunction "COM_9") (pintype "unspecified"))
      (node (ref "U7") (pin "2") (pinfunction "H_2") (pintype "unspecified"))
    )
    (net (code "2") (name "+5VA") (class "Default")
      (node (ref "C11") (pin "2") (pinfunction "2_2") (pintype "unspecified"))
      (node (ref "C12") (pin "2") (pinfunction "2_2") (pintype "unspecified"))
      (node (ref "C13") (pin "2") (pinfunction "2_2") (pintype "unspecified"))
      (node (ref "C14") (pin "2") (pinfunction "2_2") (pintype "unspecified"))
      (node (ref "C15") (pin "2") (pinfunction "2_2") (pintype "unspecified"))
      (node (ref "C18") (pin "2") (pinfunction "2_2") (pintype "unspecified"))
      (node (ref "C19") (pin "2") (pinfunction "2_2") (pintype "unspecified"))
      (node (ref "C2") (pin "2") (pinfunction "2_2") (pintype "unspecified"))
      (node (ref "C20") (pin "2") (pinfunction "2_2") (pintype "unspecified"))
      (node (ref "C23") (pin "2") (pinfunction "2_2") (pintype "unspecified"))
      (node (ref "C24") (pin "2") (pinfunction "2_2") (pintype "unspecified"))
      (node (ref "C25") (pin "2") (pinfunction "2_2") (pintype "unspecified"))
      (node (ref "C28") (pin "2") (pinfunction "2_2") (pintype "unspecified"))
      (node (ref "C29") (pin "2") (pinfunction "2_2") (pintype "unspecified"))
      (node (ref "C30") (pin "2") (pinfunction "2_2") (pintype "unspecified"))
      (node (ref "C33") (pin "2") (pinfunction "2_2") (pintype "unspecified"))
      (node (ref "C34") (pin "2") (pinfunction "2_2") (pintype "unspecified"))
      (node (ref "C35") (pin "2") (pinfunction "2_2") (pintype "unspecified"))
      (node (ref "C38") (pin "2") (pinfunction "2_2") (pintype "unspecified"))
      (node (ref "C39") (pin "2") (pinfunction "2_2") (pintype "unspecified"))
      (node (ref "C40") (pin "2") (pinfunction "2_2") (pintype "unspecified"))
      (node (ref "C46") (pin "2") (pinfunction "2_2") (pintype "unspecified"))
      (node (ref "C52") (pin "2") (pinfunction "2_2") (pintype "unspecified"))
      (node (ref "C6") (pin "2") (pinfunction "2_2") (pintype "unspecified"))
      (node (ref "C62") (pin "2") (pinfunction "2_2") (pintype "unspecified"))
      (node (ref "C63") (pin "1") (pinfunction "1_1") (pintype "input"))
      (node (ref "C64") (pin "2") (pinfunction "2_2") (pintype "unspecified"))
      (node (ref "C7") (pin "2") (pinfunction "2_2") (pintype "unspecified"))
      (node (ref "C8") (pin "2") (pinfunction "2_2") (pintype "unspecified"))
      (node (ref "L1") (pin "1") (pinfunction "1_1") (pintype "unspecified"))
      (node (ref "R15") (pin "1") (pinfunction "1_1") (pintype "input"))
      (node (ref "R16") (pin "1") (pinfunction "1_1") (pintype "input"))
      (node (ref "R17") (pin "2") (pinfunction "2_2") (pintype "input"))
      (node (ref "R22") (pin "1") (pinfunction "1_1") (pintype "input"))
      (node (ref "R23") (pin "1") (pinfunction "1_1") (pintype "input"))
      (node (ref "R26") (pin "1") (pinfunction "1_1") (pintype "input"))
      (node (ref "R27") (pin "1") (pinfunction "1_1") (pintype "input"))
      (node (ref "R28") (pin "2") (pinfunction "2_2") (pintype "input"))
      (node (ref "R3") (pin "1") (pinfunction "1_1") (pintype "input"))
      (node (ref "R34") (pin "1") (pinfunction "1_1") (pintype "input"))
      (node (ref "R35") (pin "1") (pinfunction "1_1") (pintype "input"))
      (node (ref "R36") (pin "2") (pinfunction "2_2") (pintype "input"))
      (node (ref "R4") (pin "1") (pinfunction "1_1") (pintype "input"))
      (node (ref "R42") (pin "1") (pinfunction "1_1") (pintype "input"))
      (node (ref "R43") (pin "1") (pinfunction "1_1") (pintype "input"))
      (node (ref "R44") (pin "2") (pinfunction "2_2") (pintype "input"))
      (node (ref "R5") (pin "2") (pinfunction "2_2") (pintype "input"))
      (node (ref "R50") (pin "1") (pinfunction "1_1") (pintype "input"))
      (node (ref "R51") (pin "1") (pinfunction "1_1") (pintype "input"))
      (node (ref "R52") (pin "2") (pinfunction "2_2") (pintype "input"))
      (node (ref "R58") (pin "1") (pinfunction "1_1") (pintype "input"))
      (node (ref "R59") (pin "1") (pinfunction "1_1") (pintype "input"))
      (node (ref "R60") (pin "2") (pinfunction "2_2") (pintype "input"))
      (node (ref "R7") (pin "2") (pinfunction "2_2") (pintype "input"))
      (node (ref "R78") (pin "2") (pinfunction "2_2") (pintype "input"))
      (node (ref "U10") (pin "5") (pinfunction "V+_5") (pintype "passive"))
      (node (ref "U11") (pin "3") (pinfunction "VDD_3") (pintype "unspecified"))
      (node (ref "U13") (pin "7") (pinfunction "V+_7") (pintype "unspecified"))
      (node (ref "U14") (pin "5") (pinfunction "V+_5") (pintype "passive"))
      (node (ref "U15") (pin "3") (pinfunction "VDD_3") (pintype "unspecified"))
      (node (ref "U17") (pin "7") (pinfunction "V+_7") (pintype "unspecified"))
      (node (ref "U18") (pin "5") (pinfunction "V+_5") (pintype "passive"))
      (node (ref "U19") (pin "3") (pinfunction "VDD_3") (pintype "unspecified"))
      (node (ref "U2") (pin "7") (pinfunction "V+_7") (pintype "unspecified"))
      (node (ref "U21") (pin "7") (pinfunction "V+_7") (pintype "unspecified"))
      (node (ref "U22") (pin "5") (pinfunction "V+_5") (pintype "passive"))
      (node (ref "U23") (pin "3") (pinfunction "VDD_3") (pintype "unspecified"))
      (node (ref "U25") (pin "7") (pinfunction "V+_7") (pintype "unspecified"))
      (node (ref "U26") (pin "5") (pinfunction "V+_5") (pintype "passive"))
      (node (ref "U27") (pin "3") (pinfunction "VDD_3") (pintype "unspecified"))
      (node (ref "U29") (pin "7") (pinfunction "V+_7") (pintype "unspecified"))
      (node (ref "U3") (pin "7") (pinfunction "V+_7") (pintype "unspecified"))
      (node (ref "U30") (pin "5") (pinfunction "V+_5") (pintype "passive"))
      (node (ref "U31") (pin "3") (pinfunction "VDD_3") (pintype "unspecified"))
      (node (ref "U34") (pin "5") (pinfunction "V+_5") (pintype "passive"))
      (node (ref "U35") (pin "1") (pinfunction "AVDD_1") (pintype "passive"))
      (node (ref "U37") (pin "5") (pinfunction "V+_5") (pintype "passive"))
      (node (ref "U38") (pin "3") (pinfunction "VIN_3") (pintype "unspecified"))
      (node (ref "U4") (pin "5") (pinfunction "V+_5") (pintype "passive"))
      (node (ref "U5") (pin "5") (pinfunction "V+_5") (pintype "passive"))
      (node (ref "U6") (pin "3") (pinfunction "VDD_3") (pintype "unspecified"))
      (node (ref "U8") (pin "3") (pinfunction "VDD_3") (pintype "unspecified"))
      (node (ref "U9") (pin "7") (pinfunction "V+_7") (pintype "unspecified"))
    )
    (net (code "3") (name "3V3AON") (class "Default")
      (node (ref "C100") (pin "2") (pinfunction "2_2") (pintype "unspecified"))
      (node (ref "C101") (pin "2") (pinfunction "2_2") (pintype "unspecified"))
      (node (ref "C98") (pin "2") (pinfunction "2_2") (pintype "unspecified"))
      (node (ref "C99") (pin "2") (pinfunction "2_2") (pintype "unspecified"))
      (node (ref "R106") (pin "1") (pinfunction "1_1") (pintype "input"))
      (node (ref "R107") (pin "2") (pinfunction "2_2") (pintype "input"))
      (node (ref "U42") (pin "5") (pinfunction "OUT_5") (pintype "unspecified"))
      (node (ref "U46") (pin "1") (pinfunction "VDD_1") (pintype "unspecified"))
      (node (ref "U51") (pin "8") (pinfunction "VCC_8") (pintype "unspecified"))
      (node (ref "U52") (pin "5") (pinfunction "VCC_5") (pintype "unspecified"))
    )
    (net (code "4") (name "5VBUCK") (class "Default")
      (node (ref "C72") (pin "2") (pinfunction "2_2") (pintype "unspecified"))
      (node (ref "C73") (pin "2") (pinfunction "2_2") (pintype "unspecified"))
      (node (ref "D3") (pin "2") (pinfunction "A2_2") (pintype "unspecified"))
      (node (ref "D8") (pin "1") (pinfunction "A_1") (pintype "unspecified"))
      (node (ref "R85") (pin "2") (pinfunction "2_2") (pintype "input"))
      (node (ref "R87") (pin "2") (pinfunction "2_2") (pintype "input"))
      (node (ref "U40") (pin "2") (pinfunction "2_2") (pintype "unspecified"))
    )
    (net (code "5") (name "5VEXT") (class "Default")
      (node (ref "D7") (pin "1") (pinfunction "A_1") (pintype "unspecified"))
      (node (ref "J1") (pin "4") (pinfunction "4_4") (pintype "input"))
    )
    (net (code "6") (name "A") (class "Default")
      (node (ref "CN3") (pin "2") (pinfunction "2_2") (pintype "unspecified"))
      (node (ref "D6") (pin "2") (pinfunction "2_2") (pintype "unspecified"))
      (node (ref "U47") (pin "6") (pinfunction "A_6") (pintype "unspecified"))
    )
    (net (code "7") (name "AGND") (class "Default")
      (node (ref "C67") (pin "2") (pinfunction "2_2") (pintype "unspecified"))
      (node (ref "C68") (pin "2") (pinfunction "2_2") (pintype "unspecified"))
      (node (ref "R10") (pin "1") (pinfunction "1_1") (pintype "input"))
      (node (ref "R20") (pin "1") (pinfunction "1_1") (pintype "input"))
      (node (ref "R31") (pin "1") (pinfunction "1_1") (pintype "input"))
      (node (ref "R39") (pin "1") (pinfunction "1_1") (pintype "input"))
      (node (ref "R47") (pin "1") (pinfunction "1_1") (pintype "input"))
      (node (ref "R55") (pin "1") (pinfunction "1_1") (pintype "input"))
      (node (ref "R6") (pin "1") (pinfunction "1_1") (pintype "input"))
      (node (ref "R63") (pin "1") (pinfunction "1_1") (pintype "input"))
      (node (ref "U1") (pin "1") (pinfunction "A_1") (pintype "unspecified"))
      (node (ref "U1") (pin "3") (pinfunction "A_3") (pintype "unspecified"))
      (node (ref "U12") (pin "1") (pinfunction "A_1") (pintype "unspecified"))
      (node (ref "U12") (pin "3") (pinfunction "A_3") (pintype "unspecified"))
      (node (ref "U16") (pin "1") (pinfunction "A_1") (pintype "unspecified"))
      (node (ref "U16") (pin "3") (pinfunction "A_3") (pintype "unspecified"))
      (node (ref "U20") (pin "1") (pinfunction "A_1") (pintype "unspecified"))
      (node (ref "U20") (pin "3") (pinfunction "A_3") (pintype "unspecified"))
      (node (ref "U24") (pin "1") (pinfunction "A_1") (pintype "unspecified"))
      (node (ref "U24") (pin "3") (pinfunction "A_3") (pintype "unspecified"))
      (node (ref "U28") (pin "1") (pinfunction "A_1") (pintype "unspecified"))
      (node (ref "U28") (pin "3") (pinfunction "A_3") (pintype "unspecified"))
      (node (ref "U32") (pin "1") (pinfunction "A_1") (pintype "unspecified"))
      (node (ref "U32") (pin "3") (pinfunction "A_3") (pintype "unspecified"))
      (node (ref "U34") (pin "1") (pinfunction "OUT_1") (pintype "output"))
      (node (ref "U34") (pin "4") (pinfunction "IN-_4") (pintype "unspecified"))
      (node (ref "U7") (pin "1") (pinfunction "A_1") (pintype "unspecified"))
      (node (ref "U7") (pin "3") (pinfunction "A_3") (pintype "unspecified"))
    )
    (net (code "8") (name "AI0") (class "Default")
      (node (ref "C41") (pin "2") (pinfunction "2_2") (pintype "unspecified"))
      (node (ref "R65") (pin "1") (pinfunction "1_1") (pintype "unspecified"))
      (node (ref "U35") (pin "6") (pinfunction "AIN0_6") (pintype "unspecified"))
    )
    (net (code "9") (name "AI1") (class "Default")
      (node (ref "C42") (pin "2") (pinfunction "2_2") (pintype "unspecified"))
      (node (ref "R66") (pin "1") (pinfunction "1_1") (pintype "unspecified"))
      (node (ref "U35") (pin "7") (pinfunction "AIN1_7") (pintype "unspecified"))
    )
    (net (code "10") (name "AI2") (class "Default")
      (node (ref "C43") (pin "2") (pinfunction "2_2") (pintype "unspecified"))
      (node (ref "R67") (pin "1") (pinfunction "1_1") (pintype "unspecified"))
      (node (ref "U35") (pin "8") (pinfunction "AIN2_8") (pintype "unspecified"))
    )
    (net (code "11") (name "AI3") (class "Default")
      (node (ref "C44") (pin "2") (pinfunction "2_2") (pintype "unspecified"))
      (node (ref "R68") (pin "1") (pinfunction "1_1") (pintype "unspecified"))
      (node (ref "U35") (pin "9") (pinfunction "AIN3_9") (pintype "unspecified"))
    )
    (net (code "12") (name "AI4") (class "Default")
      (node (ref "C47") (pin "2") (pinfunction "2_2") (pintype "unspecified"))
      (node (ref "R69") (pin "1") (pinfunction "1_1") (pintype "unspecified"))
      (node (ref "U35") (pin "10") (pinfunction "AIN4_10") (pintype "unspecified"))
    )
    (net (code "13") (name "AI5") (class "Default")
      (node (ref "C48") (pin "2") (pinfunction "2_2") (pintype "unspecified"))
      (node (ref "R70") (pin "1") (pinfunction "1_1") (pintype "unspecified"))
      (node (ref "U35") (pin "11") (pinfunction "AIN5_11") (pintype "unspecified"))
    )
    (net (code "14") (name "AI6") (class "Default")
      (node (ref "C49") (pin "2") (pinfunction "2_2") (pintype "unspecified"))
      (node (ref "R71") (pin "1") (pinfunction "1_1") (pintype "unspecified"))
      (node (ref "U35") (pin "12") (pinfunction "AIN6_12") (pintype "unspecified"))
    )
    (net (code "15") (name "AI7") (class "Default")
      (node (ref "C50") (pin "2") (pinfunction "2_2") (pintype "unspecified"))
      (node (ref "R72") (pin "1") (pinfunction "1_1") (pintype "unspecified"))
      (node (ref "U35") (pin "13") (pinfunction "AIN7_13") (pintype "unspecified"))
    )
    (net (code "16") (name "AIN0") (class "Default")
      (node (ref "R65") (pin "2") (pinfunction "2_2") (pintype "unspecified"))
      (node (ref "U2") (pin "6") (pinfunction "VOUT_6") (pintype "unspecified"))
    )
    (net (code "17") (name "AIN1") (class "Default")
      (node (ref "R66") (pin "2") (pinfunction "2_2") (pintype "unspecified"))
      (node (ref "U3") (pin "6") (pinfunction "VOUT_6") (pintype "unspecified"))
    )
    (net (code "18") (name "AIN2") (class "Default")
      (node (ref "R67") (pin "2") (pinfunction "2_2") (pintype "unspecified"))
      (node (ref "U9") (pin "6") (pinfunction "VOUT_6") (pintype "unspecified"))
    )
    (net (code "19") (name "AIN3") (class "Default")
      (node (ref "R68") (pin "2") (pinfunction "2_2") (pintype "unspecified"))
      (node (ref "U25") (pin "6") (pinfunction "VOUT_6") (pintype "unspecified"))
    )
    (net (code "20") (name "AIN4") (class "Default")
      (node (ref "R69") (pin "2") (pinfunction "2_2") (pintype "unspecified"))
      (node (ref "U29") (pin "6") (pinfunction "VOUT_6") (pintype "unspecified"))
    )
    (net (code "21") (name "AIN5") (class "Default")
      (node (ref "R70") (pin "2") (pinfunction "2_2") (pintype "unspecified"))
      (node (ref "U21") (pin "6") (pinfunction "VOUT_6") (pintype "unspecified"))
    )
    (net (code "22") (name "AIN6") (class "Default")
      (node (ref "R71") (pin "2") (pinfunction "2_2") (pintype "unspecified"))
      (node (ref "U17") (pin "6") (pinfunction "VOUT_6") (pintype "unspecified"))
    )
    (net (code "23") (name "AIN7") (class "Default")
      (node (ref "R72") (pin "2") (pinfunction "2_2") (pintype "unspecified"))
      (node (ref "U13") (pin "6") (pinfunction "VOUT_6") (pintype "unspecified"))
    )
    (net (code "24") (name "ANT") (class "Default")
      (node (ref "G$1") (pin "SIG") (pinfunction "SIG_SIG") (pintype "bidirectional"))
      (node (ref "U45") (pin "6") (pinfunction "ANT_6") (pintype "unspecified"))
    )
    (net (code "25") (name "B") (class "Default")
      (node (ref "CN3") (pin "1") (pinfunction "1_1") (pintype "unspecified"))
      (node (ref "D6") (pin "1") (pinfunction "1_1") (pintype "unspecified"))
      (node (ref "U47") (pin "7") (pinfunction "B_7") (pintype "unspecified"))
    )
    (net (code "26") (name "BATMON") (class "Default")
      (node (ref "C71") (pin "2") (pinfunction "2_2") (pintype "unspecified"))
      (node (ref "R82") (pin "2") (pinfunction "2_2") (pintype "input"))
      (node (ref "R83") (pin "1") (pinfunction "1_1") (pintype "input"))
      (node (ref "U49") (pin "4") (pinfunction "IO4_4") (pintype "unspecified"))
    )
    (net (code "27") (name "BUZZER") (class "Default")
      (node (ref "U44") (pin "3") (pinfunction "I3_3") (pintype "unspecified"))
      (node (ref "U49") (pin "33") (pinfunction "IO40_33") (pintype "unspecified"))
    )
    (net (code "28") (name "CFG") (class "Default")
      (node (ref "R80") (pin "2") (pinfunction "2_2") (pintype "input"))
      (node (ref "SW1") (pin "1") (pinfunction "1_1") (pintype "input"))
      (node (ref "U49") (pin "9") (pinfunction "IO16_9") (pintype "unspecified"))
    )
    (net (code "29") (name "CLR") (class "Default")
      (node (ref "R107") (pin "1") (pinfunction "1_1") (pintype "input"))
      (node (ref "U49") (pin "31") (pinfunction "IO38_31") (pintype "unspecified"))
      (node (ref "U51") (pin "6") (pinfunction "#CLR_6") (pintype "unspecified"))
    )
    (net (code "30") (name "D+") (class "Default")
      (node (ref "D5") (pin "2") (pinfunction "2_2") (pintype "unspecified"))
      (node (ref "U48") (pin "5") (pinfunction "D+_5") (pintype "unspecified"))
      (node (ref "USB1") (pin "3") (pinfunction "D+_3") (pintype "unspecified"))
    )
    (net (code "31") (name "D-") (class "Default")
      (node (ref "D4") (pin "2") (pinfunction "2_2") (pintype "unspecified"))
      (node (ref "U48") (pin "6") (pinfunction "D-_6") (pintype "unspecified"))
      (node (ref "USB1") (pin "2") (pinfunction "D-_2") (pintype "unspecified"))
    )
    (net (code "32") (name "DCFAN") (class "Default")
      (node (ref "U44") (pin "1") (pinfunction "I1_1") (pintype "unspecified"))
      (node (ref "U49") (pin "35") (pinfunction "IO42_35") (pintype "unspecified"))
    )
    (net (code "33") (name "DIO1") (class "Default")
      (node (ref "U45") (pin "20") (pinfunction "DIO1_20") (pintype "unspecified"))
      (node (ref "U49") (pin "39") (pinfunction "IO1_39") (pintype "unspecified"))
    )
    (net (code "34") (name "DIR") (class "Default")
      (node (ref "U47") (pin "2") (pinfunction "RE#_2") (pintype "unspecified"))
      (node (ref "U47") (pin "3") (pinfunction "DE_3") (pintype "unspecified"))
      (node (ref "U49") (pin "13") (pinfunction "IO19_13") (pintype "unspecified"))
    )
    (net (code "35") (name "DONE") (class "Default")
      (node (ref "U46") (pin "4") (pinfunction "DONE_4") (pintype "unspecified"))
      (node (ref "U49") (pin "22") (pinfunction "IO14_22") (pintype "unspecified"))
    )
    (net (code "36") (name "DRDY") (class "Default")
      (node (ref "U35") (pin "21") (pinfunction "DRDY_21") (pintype "output"))
      (node (ref "U49") (pin "18") (pinfunction "IO10_18") (pintype "unspecified"))
    )
    (net (code "37") (name "DTR") (class "Default")
      (node (ref "Q1") (pin "2") (pinfunction "B1_2") (pintype "unspecified"))
      (node (ref "Q1") (pin "4") (pinfunction "E2_4") (pintype "unspecified"))
      (node (ref "U48") (pin "13") (pinfunction "DTR#_13") (pintype "unspecified"))
    )
    (net (code "38") (name "ENA") (class "Default")
      (node (ref "U41") (pin "2") (pinfunction "EN_2") (pintype "unspecified"))
      (node (ref "U51") (pin "5") (pinfunction "Q_5") (pintype "unspecified"))
    )
    (net (code "39") (name "GND") (class "Default")
      (node (ref "C100") (pin "1") (pinfunction "1_1") (pintype "unspecified"))
      (node (ref "C101") (pin "1") (pinfunction "1_1") (pintype "unspecified"))
      (node (ref "C11") (pin "1") (pinfunction "1_1") (pintype "unspecified"))
      (node (ref "C12") (pin "1") (pinfunction "1_1") (pintype "unspecified"))
      (node (ref "C13") (pin "1") (pinfunction "1_1") (pintype "unspecified"))
      (node (ref "C14") (pin "1") (pinfunction "1_1") (pintype "unspecified"))
      (node (ref "C15") (pin "1") (pinfunction "1_1") (pintype "unspecified"))
      (node (ref "C16") (pin "2") (pinfunction "2_2") (pintype "unspecified"))
      (node (ref "C18") (pin "1") (pinfunction "1_1") (pintype "unspecified"))
      (node (ref "C19") (pin "1") (pinfunction "1_1") (pintype "unspecified"))
      (node (ref "C2") (pin "1") (pinfunction "1_1") (pintype "unspecified"))
      (node (ref "C20") (pin "1") (pinfunction "1_1") (pintype "unspecified"))
      (node (ref "C21") (pin "2") (pinfunction "2_2") (pintype "unspecified"))
      (node (ref "C23") (pin "1") (pinfunction "1_1") (pintype "unspecified"))
      (node (ref "C24") (pin "1") (pinfunction "1_1") (pintype "unspecified"))
      (node (ref "C25") (pin "1") (pinfunction "1_1") (pintype "unspecified"))
      (node (ref "C26") (pin "2") (pinfunction "2_2") (pintype "unspecified"))
      (node (ref "C28") (pin "1") (pinfunction "1_1") (pintype "unspecified"))
      (node (ref "C29") (pin "1") (pinfunction "1_1") (pintype "unspecified"))
      (node (ref "C3") (pin "2") (pinfunction "2_2") (pintype "unspecified"))
      (node (ref "C30") (pin "1") (pinfunction "1_1") (pintype "unspecified"))
      (node (ref "C31") (pin "2") (pinfunction "2_2") (pintype "unspecified"))
      (node (ref "C33") (pin "1") (pinfunction "1_1") (pintype "unspecified"))
      (node (ref "C34") (pin "1") (pinfunction "1_1") (pintype "unspecified"))
      (node (ref "C35") (pin "1") (pinfunction "1_1") (pintype "unspecified"))
      (node (ref "C36") (pin "2") (pinfunction "2_2") (pintype "unspecified"))
      (node (ref "C38") (pin "1") (pinfunction "1_1") (pintype "unspecified"))
      (node (ref "C39") (pin "1") (pinfunction "1_1") (pintype "unspecified"))
      (node (ref "C4") (pin "2") (pinfunction "2_2") (pintype "unspecified"))
      (node (ref "C40") (pin "1") (pinfunction "1_1") (pintype "unspecified"))
      (node (ref "C41") (pin "1") (pinfunction "1_1") (pintype "unspecified"))
      (node (ref "C42") (pin "1") (pinfunction "1_1") (pintype "unspecified"))
      (node (ref "C43") (pin "1") (pinfunction "1_1") (pintype "unspecified"))
      (node (ref "C44") (pin "1") (pinfunction "1_1") (pintype "unspecified"))
      (node (ref "C45") (pin "2") (pinfunction "2_2") (pintype "input"))
      (node (ref "C46") (pin "1") (pinfunction "1_1") (pintype "unspecified"))
      (node (ref "C47") (pin "1") (pinfunction "1_1") (pintype "unspecified"))
      (node (ref "C48") (pin "1") (pinfunction "1_1") (pintype "unspecified"))
      (node (ref "C49") (pin "1") (pinfunction "1_1") (pintype "unspecified"))
      (node (ref "C50") (pin "1") (pinfunction "1_1") (pintype "unspecified"))
      (node (ref "C51") (pin "1") (pinfunction "1_1") (pintype "unspecified"))
      (node (ref "C52") (pin "1") (pinfunction "1_1") (pintype "unspecified"))
      (node (ref "C53") (pin "2") (pinfunction "2_2") (pintype "input"))
      (node (ref "C54") (pin "1") (pinfunction "1_1") (pintype "unspecified"))
      (node (ref "C55") (pin "1") (pinfunction "1_1") (pintype "unspecified"))
      (node (ref "C56") (pin "2") (pinfunction "2_2") (pintype "input"))
      (node (ref "C57") (pin "1") (pinfunction "1_1") (pintype "input"))
      (node (ref "C58") (pin "1") (pinfunction "1_1") (pintype "unspecified"))
      (node (ref "C59") (pin "1") (pinfunction "1_1") (pintype "unspecified"))
      (node (ref "C6") (pin "1") (pinfunction "1_1") (pintype "unspecified"))
      (node (ref "C60") (pin "1") (pinfunction "1_1") (pintype "unspecified"))
      (node (ref "C61") (pin "1") (pinfunction "1_1") (pintype "unspecified"))
      (node (ref "C62") (pin "1") (pinfunction "1_1") (pintype "unspecified"))
      (node (ref "C63") (pin "2") (pinfunction "2_2") (pintype "input"))
      (node (ref "C64") (pin "1") (pinfunction "1_1") (pintype "unspecified"))
      (node (ref "C65") (pin "1") (pinfunction "1_1") (pintype "unspecified"))
      (node (ref "C66") (pin "1") (pinfunction "1_1") (pintype "unspecified"))
      (node (ref "C67") (pin "1") (pinfunction "1_1") (pintype "unspecified"))
      (node (ref "C68") (pin "1") (pinfunction "1_1") (pintype "unspecified"))
      (node (ref "C7") (pin "1") (pinfunction "1_1") (pintype "unspecified"))
      (node (ref "C71") (pin "1") (pinfunction "1_1") (pintype "unspecified"))
      (node (ref "C72") (pin "1") (pinfunction "1_1") (pintype "unspecified"))
      (node (ref "C73") (pin "1") (pinfunction "1_1") (pintype "unspecified"))
      (node (ref "C74") (pin "1") (pinfunction "1_1") (pintype "unspecified"))
      (node (ref "C75") (pin "1") (pinfunction "1_1") (pintype "unspecified"))
      (node (ref "C77") (pin "1") (pinfunction "1_1") (pintype "input"))
      (node (ref "C78") (pin "1") (pinfunction "1_1") (pintype "unspecified"))
      (node (ref "C79") (pin "1") (pinfunction "1_1") (pintype "unspecified"))
      (node (ref "C8") (pin "1") (pinfunction "1_1") (pintype "unspecified"))
      (node (ref "C80") (pin "1") (pinfunction "1_1") (pintype "unspecified"))
      (node (ref "C81") (pin "1") (pinfunction "1_1") (pintype "unspecified"))
      (node (ref "C82") (pin "2") (pinfunction "2_2") (pintype "input"))
      (node (ref "C83") (pin "2") (pinfunction "2_2") (pintype "input"))
      (node (ref "C84") (pin "1") (pinfunction "1_1") (pintype "input"))
      (node (ref "C85") (pin "1") (pinfunction "1_1") (pintype "unspecified"))
      (node (ref "C86") (pin "1") (pinfunction "1_1") (pintype "unspecified"))
      (node (ref "C87") (pin "1") (pinfunction "1_1") (pintype "unspecified"))
      (node (ref "C88") (pin "1") (pinfunction "1_1") (pintype "unspecified"))
      (node (ref "C89") (pin "1") (pinfunction "1_1") (pintype "unspecified"))
      (node (ref "C9") (pin "2") (pinfunction "2_2") (pintype "unspecified"))
      (node (ref "C90") (pin "1") (pinfunction "1_1") (pintype "unspecified"))
      (node (ref "C91") (pin "1") (pinfunction "1_1") (pintype "unspecified"))
      (node (ref "C92") (pin "1") (pinfunction "1_1") (pintype "unspecified"))
      (node (ref "C93") (pin "1") (pinfunction "1_1") (pintype "input"))
      (node (ref "C94") (pin "1") (pinfunction "1_1") (pintype "unspecified"))
      (node (ref "C95") (pin "1") (pinfunction "1_1") (pintype "unspecified"))
      (node (ref "C96") (pin "1") (pinfunction "1_1") (pintype "unspecified"))
      (node (ref "C97") (pin "1") (pinfunction "1_1") (pintype "unspecified"))
      (node (ref "C98") (pin "1") (pinfunction "1_1") (pintype "unspecified"))
      (node (ref "C99") (pin "1") (pinfunction "1_1") (pintype "unspecified"))
      (node (ref "CN2") (pin "2") (pinfunction "2_2") (pintype "unspecified"))
      (node (ref "D1") (pin "2") (pinfunction "A_2") (pintype "unspecified"))
      (node (ref "D4") (pin "1") (pinfunction "1_1") (pintype "unspecified"))
      (node (ref "D5") (pin "1") (pinfunction "1_1") (pintype "unspecified"))
      (node (ref "D6") (pin "3") (pinfunction "3_3") (pintype "unspecified"))
      (node (ref "G$1") (pin "GND1") (pinfunction "GND_GND1") (pintype "bidirectional"))
      (node (ref "G$1") (pin "GND2") (pinfunction "GND_GND2") (pintype "bidirectional"))
      (node (ref "J2") (pin "4") (pinfunction "4_4") (pintype "unspecified"))
      (node (ref "R105") (pin "1") (pinfunction "1_1") (pintype "input"))
      (node (ref "R79") (pin "1") (pinfunction "1_1") (pintype "input"))
      (node (ref "R81") (pin "1") (pinfunction "1_1") (pintype "input"))
      (node (ref "R82") (pin "1") (pinfunction "1_1") (pintype "input"))
      (node (ref "R86") (pin "1") (pinfunction "1_1") (pintype "input"))
      (node (ref "R89") (pin "2") (pinfunction "2_2") (pintype "input"))
      (node (ref "R92") (pin "1") (pinfunction "1_1") (pintype "input"))
      (node (ref "R99") (pin "2") (pinfunction "2_2") (pintype "input"))
      (node (ref "SW1") (pin "2") (pinfunction "2_2") (pintype "input"))
      (node (ref "U1") (pin "6") (pinfunction "H_6") (pintype "unspecified"))
      (node (ref "U10") (pin "2") (pinfunction "V-_2") (pintype "passive"))
      (node (ref "U11") (pin "2") (pinfunction "VSS_2") (pintype "unspecified"))
      (node (ref "U11") (pin "6") (pinfunction "A0_6") (pintype "unspecified"))
      (node (ref "U12") (pin "6") (pinfunction "H_6") (pintype "unspecified"))
      (node (ref "U13") (pin "4") (pinfunction "V-_4") (pintype "unspecified"))
      (node (ref "U14") (pin "2") (pinfunction "V-_2") (pintype "passive"))
      (node (ref "U15") (pin "2") (pinfunction "VSS_2") (pintype "unspecified"))
      (node (ref "U15") (pin "6") (pinfunction "A0_6") (pintype "unspecified"))
      (node (ref "U16") (pin "6") (pinfunction "H_6") (pintype "unspecified"))
      (node (ref "U17") (pin "4") (pinfunction "V-_4") (pintype "unspecified"))
      (node (ref "U18") (pin "2") (pinfunction "V-_2") (pintype "passive"))
      (node (ref "U19") (pin "2") (pinfunction "VSS_2") (pintype "unspecified"))
      (node (ref "U19") (pin "6") (pinfunction "A0_6") (pintype "unspecified"))
      (node (ref "U2") (pin "4") (pinfunction "V-_4") (pintype "unspecified"))
      (node (ref "U20") (pin "6") (pinfunction "H_6") (pintype "unspecified"))
      (node (ref "U21") (pin "4") (pinfunction "V-_4") (pintype "unspecified"))
      (node (ref "U22") (pin "2") (pinfunction "V-_2") (pintype "passive"))
      (node (ref "U23") (pin "2") (pinfunction "VSS_2") (pintype "unspecified"))
      (node (ref "U23") (pin "6") (pinfunction "A0_6") (pintype "unspecified"))
      (node (ref "U24") (pin "6") (pinfunction "H_6") (pintype "unspecified"))
      (node (ref "U25") (pin "4") (pinfunction "V-_4") (pintype "unspecified"))
      (node (ref "U26") (pin "2") (pinfunction "V-_2") (pintype "passive"))
      (node (ref "U27") (pin "2") (pinfunction "VSS_2") (pintype "unspecified"))
      (node (ref "U27") (pin "6") (pinfunction "A0_6") (pintype "unspecified"))
      (node (ref "U28") (pin "6") (pinfunction "H_6") (pintype "unspecified"))
      (node (ref "U29") (pin "4") (pinfunction "V-_4") (pintype "unspecified"))
      (node (ref "U3") (pin "4") (pinfunction "V-_4") (pintype "unspecified"))
      (node (ref "U30") (pin "2") (pinfunction "V-_2") (pintype "passive"))
      (node (ref "U31") (pin "2") (pinfunction "VSS_2") (pintype "unspecified"))
      (node (ref "U31") (pin "6") (pinfunction "A0_6") (pintype "unspecified"))
      (node (ref "U32") (pin "6") (pinfunction "H_6") (pintype "unspecified"))
      (node (ref "U33") (pin "12") (pinfunction "GND_12") (pintype "unspecified"))
      (node (ref "U33") (pin "2") (pinfunction "A1_2") (pintype "unspecified"))
      (node (ref "U33") (pin "21") (pinfunction "A2_21") (pintype "unspecified"))
      (node (ref "U34") (pin "2") (pinfunction "V-_2") (pintype "passive"))
      (node (ref "U35") (pin "17") (pinfunction "DGND_17") (pintype "passive"))
      (node (ref "U35") (pin "2") (pinfunction "AGND_2") (pintype "passive"))
      (node (ref "U35") (pin "3") (pinfunction "VREFN_3") (pintype "unspecified"))
      (node (ref "U35") (pin "5") (pinfunction "AINCOM_5") (pintype "unspecified"))
      (node (ref "U36") (pin "13") (pinfunction "EP_13") (pintype "unspecified"))
      (node (ref "U36") (pin "8") (pinfunction "AGND_8") (pintype "unspecified"))
      (node (ref "U37") (pin "2") (pinfunction "V-_2") (pintype "passive"))
      (node (ref "U38") (pin "2") (pinfunction "GND_2") (pintype "unspecified"))
      (node (ref "U39") (pin "2") (pinfunction "GND_2") (pintype "input"))
      (node (ref "U39") (pin "4") (pinfunction "GND_4") (pintype "input"))
      (node (ref "U4") (pin "2") (pinfunction "V-_2") (pintype "passive"))
      (node (ref "U41") (pin "20") (pinfunction "AGND_20") (pintype "unspecified"))
      (node (ref "U41") (pin "21") (pinfunction "PGND_21") (pintype "unspecified"))
      (node (ref "U42") (pin "2") (pinfunction "GND_2") (pintype "unspecified"))
      (node (ref "U43") (pin "1") (pinfunction "PGND_1") (pintype "passive"))
      (node (ref "U43") (pin "4") (pinfunction "AGND_4") (pintype "passive"))
      (node (ref "U43") (pin "5") (pinfunction "FB_5") (pintype "unspecified"))
      (node (ref "U43") (pin "9") (pinfunction "EP_9") (pintype "passive"))
      (node (ref "U44") (pin "8") (pinfunction "GND_8") (pintype "unspecified"))
      (node (ref "U45") (pin "16") (pinfunction "GND_16") (pintype "unspecified"))
      (node (ref "U45") (pin "2") (pinfunction "GND_2") (pintype "unspecified"))
      (node (ref "U45") (pin "7") (pinfunction "GND_7") (pintype "unspecified"))
      (node (ref "U46") (pin "2") (pinfunction "GND_2") (pintype "unspecified"))
      (node (ref "U47") (pin "5") (pinfunction "GND_5") (pintype "unspecified"))
      (node (ref "U48") (pin "1") (pinfunction "GND_1") (pintype "unspecified"))
      (node (ref "U49") (pin "1") (pinfunction "GND_1") (pintype "passive"))
      (node (ref "U49") (pin "40") (pinfunction "GND_40") (pintype "passive"))
      (node (ref "U49") (pin "41") (pinfunction "GND_41") (pintype "passive"))
      (node (ref "U5") (pin "2") (pinfunction "V-_2") (pintype "passive"))
      (node (ref "U51") (pin "4") (pinfunction "GND_4") (pintype "unspecified"))
      (node (ref "U52") (pin "3") (pinfunction "GND_3") (pintype "unspecified"))
      (node (ref "U6") (pin "2") (pinfunction "VSS_2") (pintype "unspecified"))
      (node (ref "U6") (pin "6") (pinfunction "A0_6") (pintype "unspecified"))
      (node (ref "U7") (pin "6") (pinfunction "H_6") (pintype "unspecified"))
      (node (ref "U8") (pin "2") (pinfunction "VSS_2") (pintype "unspecified"))
      (node (ref "U8") (pin "6") (pinfunction "A0_6") (pintype "unspecified"))
      (node (ref "U9") (pin "4") (pinfunction "V-_4") (pintype "unspecified"))
      (node (ref "USB1") (pin "5") (pinfunction "GND_5") (pintype "unspecified"))
      (node (ref "USB1") (pin "6") (pinfunction "EP_6") (pintype "unspecified"))
      (node (ref "USB1") (pin "7") (pinfunction "EP_7") (pintype "unspecified"))
    )
    (net (code "40") (name "IO0") (class "Default")
      (node (ref "C90") (pin "2") (pinfunction "2_2") (pintype "unspecified"))
      (node (ref "Q1") (pin "3") (pinfunction "C2_3") (pintype "unspecified"))
      (node (ref "R94") (pin "1") (pinfunction "1_1") (pintype "input"))
      (node (ref "U49") (pin "27") (pinfunction "IO0_27") (pintype "unspecified"))
    )
    (net (code "41") (name "LAMP") (class "Default")
      (node (ref "U44") (pin "2") (pinfunction "I2_2") (pintype "unspecified"))
      (node (ref "U49") (pin "34") (pinfunction "IO41_34") (pintype "unspecified"))
    )
    (net (code "42") (name "LED") (class "Default")
      (node (ref "R93") (pin "1") (pinfunction "1_1") (pintype "input"))
      (node (ref "U49") (pin "32") (pinfunction "IO39_32") (pintype "unspecified"))
    )
    (net (code "43") (name "LORA_BUSY") (class "Default")
      (node (ref "U45") (pin "11") (pinfunction "BUSY_11") (pintype "unspecified"))
      (node (ref "U49") (pin "8") (pinfunction "IO15_8") (pintype "unspecified"))
    )
    (net (code "44") (name "LORA_RST") (class "Default")
      (node (ref "U45") (pin "3") (pinfunction "NRST_3") (pintype "unspecified"))
      (node (ref "U49") (pin "38") (pinfunction "IO2_38") (pintype "unspecified"))
    )
    (net (code "45") (name "LORA_SS") (class "Default")
      (node (ref "U45") (pin "14") (pinfunction "NSS_14") (pintype "unspecified"))
      (node (ref "U49") (pin "7") (pinfunction "IO7_7") (pintype "unspecified"))
    )
    (net (code "46") (name "Net-(C69-Pad1)") (class "Default")
      (node (ref "C69") (pin "1") (pinfunction "1_1") (pintype "unspecified"))
      (node (ref "U36") (pin "1") (pinfunction "SW_1") (pintype "unspecified"))
      (node (ref "U36") (pin "2") (pinfunction "SW_2") (pintype "unspecified"))
      (node (ref "U36") (pin "3") (pinfunction "SW_3") (pintype "unspecified"))
      (node (ref "U40") (pin "1") (pinfunction "1_1") (pintype "unspecified"))
    )
    (net (code "47") (name "Net-(C70-Pad1)") (class "Default")
      (node (ref "C70") (pin "1") (pinfunction "1_1") (pintype "input"))
      (node (ref "R87") (pin "1") (pinfunction "1_1") (pintype "input"))
    )
    (net (code "48") (name "Net-(C76-Pad2)") (class "Default")
      (node (ref "C76") (pin "2") (pinfunction "2_2") (pintype "unspecified"))
      (node (ref "L2") (pin "2") (pinfunction "2_2") (pintype "unspecified"))
      (node (ref "R88") (pin "1") (pinfunction "1_1") (pintype "input"))
      (node (ref "U41") (pin "4") (pinfunction "SW_4") (pintype "unspecified"))
      (node (ref "U41") (pin "5") (pinfunction "SW_5") (pintype "unspecified"))
      (node (ref "U41") (pin "6") (pinfunction "SW_6") (pintype "unspecified"))
      (node (ref "U41") (pin "7") (pinfunction "SW_7") (pintype "unspecified"))
    )
    (net (code "49") (name "Net-(C82-Pad1)") (class "Default")
      (node (ref "C82") (pin "1") (pinfunction "1_1") (pintype "input"))
      (node (ref "R91") (pin "2") (pinfunction "2_2") (pintype "input"))
    )
    (net (code "50") (name "Net-(CN2-Pad1)") (class "Default")
      (node (ref "CN2") (pin "1") (pinfunction "1_1") (pintype "unspecified"))
      (node (ref "J1") (pin "1") (pinfunction "1_1") (pintype "input"))
      (node (ref "J1") (pin "3") (pinfunction "3_3") (pintype "input"))
      (node (ref "J1") (pin "5") (pinfunction "5_5") (pintype "input"))
    )
    (net (code "51") (name "Net-(D1-K)") (class "Default")
      (node (ref "D1") (pin "1") (pinfunction "K_1") (pintype "unspecified"))
      (node (ref "D2") (pin "1") (pinfunction "K_1") (pintype "unspecified"))
      (node (ref "F1") (pin "2") (pinfunction "2_2") (pintype "unspecified"))
      (node (ref "Q3") (pin "1") (pinfunction "S_1") (pintype "unspecified"))
      (node (ref "Q3") (pin "2") (pinfunction "S_2") (pintype "unspecified"))
      (node (ref "Q3") (pin "3") (pinfunction "S_3") (pintype "unspecified"))
    )
    (net (code "52") (name "Net-(D2-A)") (class "Default")
      (node (ref "D2") (pin "2") (pinfunction "A_2") (pintype "unspecified"))
      (node (ref "Q3") (pin "4") (pinfunction "G_4") (pintype "unspecified"))
      (node (ref "R81") (pin "2") (pinfunction "2_2") (pintype "input"))
    )
    (net (code "53") (name "Net-(D3-K)") (class "Default")
      (node (ref "C97") (pin "2") (pinfunction "2_2") (pintype "unspecified"))
      (node (ref "D3") (pin "3") (pinfunction "K_3") (pintype "unspecified"))
      (node (ref "R100") (pin "2") (pinfunction "2_2") (pintype "input"))
      (node (ref "U42") (pin "1") (pinfunction "IN_1") (pintype "unspecified"))
    )
    (net (code "54") (name "Net-(D9-A)") (class "Default")
      (node (ref "C78") (pin "2") (pinfunction "2_2") (pintype "unspecified"))
      (node (ref "C79") (pin "2") (pinfunction "2_2") (pintype "unspecified"))
      (node (ref "C80") (pin "2") (pinfunction "2_2") (pintype "unspecified"))
      (node (ref "C81") (pin "2") (pinfunction "2_2") (pintype "unspecified"))
      (node (ref "D9") (pin "1") (pinfunction "A_1") (pintype "unspecified"))
      (node (ref "R90") (pin "1") (pinfunction "1_1") (pintype "input"))
      (node (ref "U41") (pin "14") (pinfunction "VOUT_14") (pintype "unspecified"))
      (node (ref "U41") (pin "15") (pinfunction "VOUT_15") (pintype "unspecified"))
      (node (ref "U41") (pin "16") (pinfunction "VOUT_16") (pintype "unspecified"))
    )
    (net (code "55") (name "Net-(F1-Pad1)") (class "Default")
      (node (ref "F1") (pin "1") (pinfunction "1_1") (pintype "unspecified"))
      (node (ref "J1") (pin "6") (pinfunction "6_6") (pintype "input"))
    )
    (net (code "56") (name "Net-(LED1-C)") (class "Default")
      (node (ref "LED1") (pin "2") (pinfunction "C_2") (pintype "input"))
      (node (ref "R93") (pin "2") (pinfunction "2_2") (pintype "input"))
    )
    (net (code "57") (name "Net-(R1-Pad1)") (class "Default")
      (node (ref "R1") (pin "1") (pinfunction "1_1") (pintype "input"))
      (node (ref "U2") (pin "1") (pinfunction "RG_1") (pintype "unspecified"))
    )
    (net (code "58") (name "Net-(R1-Pad2)") (class "Default")
      (node (ref "R1") (pin "2") (pinfunction "2_2") (pintype "input"))
      (node (ref "U2") (pin "8") (pinfunction "RG_8") (pintype "unspecified"))
    )
    (net (code "59") (name "Net-(R2-Pad1)") (class "Default")
      (node (ref "R2") (pin "1") (pinfunction "1_1") (pintype "input"))
      (node (ref "U3") (pin "1") (pinfunction "RG_1") (pintype "unspecified"))
    )
    (net (code "60") (name "Net-(R2-Pad2)") (class "Default")
      (node (ref "R2") (pin "2") (pinfunction "2_2") (pintype "input"))
      (node (ref "U3") (pin "8") (pinfunction "RG_8") (pintype "unspecified"))
    )
    (net (code "61") (name "Net-(R3-Pad2)") (class "Default")
      (node (ref "R3") (pin "2") (pinfunction "2_2") (pintype "input"))
      (node (ref "R4") (pin "2") (pinfunction "2_2") (pintype "input"))
      (node (ref "R9") (pin "1") (pinfunction "1_1") (pintype "unspecified"))
      (node (ref "U7") (pin "5") (pinfunction "B_5") (pintype "unspecified"))
      (node (ref "U7") (pin "7") (pinfunction "B_7") (pintype "unspecified"))
    )
    (net (code "62") (name "Net-(R10-Pad2)") (class "Default")
      (node (ref "R10") (pin "2") (pinfunction "2_2") (pintype "input"))
      (node (ref "R7") (pin "1") (pinfunction "1_1") (pintype "input"))
      (node (ref "R8") (pin "1") (pinfunction "1_1") (pintype "unspecified"))
    )
    (net (code "63") (name "Net-(R11-Pad1)") (class "Default")
      (node (ref "R11") (pin "1") (pinfunction "1_1") (pintype "unspecified"))
      (node (ref "R22") (pin "2") (pinfunction "2_2") (pintype "input"))
      (node (ref "R23") (pin "2") (pinfunction "2_2") (pintype "input"))
      (node (ref "U1") (pin "5") (pinfunction "B_5") (pintype "unspecified"))
      (node (ref "U1") (pin "7") (pinfunction "B_7") (pintype "unspecified"))
    )
    (net (code "64") (name "Net-(R13-Pad1)") (class "Default")
      (node (ref "R13") (pin "1") (pinfunction "1_1") (pintype "input"))
      (node (ref "U9") (pin "1") (pinfunction "RG_1") (pintype "unspecified"))
    )
    (net (code "65") (name "Net-(R13-Pad2)") (class "Default")
      (node (ref "R13") (pin "2") (pinfunction "2_2") (pintype "input"))
      (node (ref "U9") (pin "8") (pinfunction "RG_8") (pintype "unspecified"))
    )
    (net (code "66") (name "Net-(R14-Pad1)") (class "Default")
      (node (ref "R14") (pin "1") (pinfunction "1_1") (pintype "unspecified"))
      (node (ref "R5") (pin "1") (pinfunction "1_1") (pintype "input"))
      (node (ref "R6") (pin "2") (pinfunction "2_2") (pintype "input"))
    )
    (net (code "67") (name "Net-(R15-Pad2)") (class "Default")
      (node (ref "R15") (pin "2") (pinfunction "2_2") (pintype "input"))
      (node (ref "R16") (pin "2") (pinfunction "2_2") (pintype "input"))
      (node (ref "R19") (pin "1") (pinfunction "1_1") (pintype "unspecified"))
      (node (ref "U12") (pin "5") (pinfunction "B_5") (pintype "unspecified"))
      (node (ref "U12") (pin "7") (pinfunction "B_7") (pintype "unspecified"))
    )
    (net (code "68") (name "Net-(R17-Pad1)") (class "Default")
      (node (ref "R17") (pin "1") (pinfunction "1_1") (pintype "input"))
      (node (ref "R18") (pin "1") (pinfunction "1_1") (pintype "unspecified"))
      (node (ref "R20") (pin "2") (pinfunction "2_2") (pintype "input"))
    )
    (net (code "69") (name "Net-(R25-Pad1)") (class "Default")
      (node (ref "R25") (pin "1") (pinfunction "1_1") (pintype "input"))
      (node (ref "U13") (pin "1") (pinfunction "RG_1") (pintype "unspecified"))
    )
    (net (code "70") (name "Net-(R25-Pad2)") (class "Default")
      (node (ref "R25") (pin "2") (pinfunction "2_2") (pintype "input"))
      (node (ref "U13") (pin "8") (pinfunction "RG_8") (pintype "unspecified"))
    )
    (net (code "71") (name "Net-(R26-Pad2)") (class "Default")
      (node (ref "R26") (pin "2") (pinfunction "2_2") (pintype "input"))
      (node (ref "R27") (pin "2") (pinfunction "2_2") (pintype "input"))
      (node (ref "R30") (pin "1") (pinfunction "1_1") (pintype "unspecified"))
      (node (ref "U16") (pin "5") (pinfunction "B_5") (pintype "unspecified"))
      (node (ref "U16") (pin "7") (pinfunction "B_7") (pintype "unspecified"))
    )
    (net (code "72") (name "Net-(R28-Pad1)") (class "Default")
      (node (ref "R28") (pin "1") (pinfunction "1_1") (pintype "input"))
      (node (ref "R29") (pin "1") (pinfunction "1_1") (pintype "unspecified"))
      (node (ref "R31") (pin "2") (pinfunction "2_2") (pintype "input"))
    )
    (net (code "73") (name "Net-(R33-Pad1)") (class "Default")
      (node (ref "R33") (pin "1") (pinfunction "1_1") (pintype "input"))
      (node (ref "U17") (pin "1") (pinfunction "RG_1") (pintype "unspecified"))
    )
    (net (code "74") (name "Net-(R33-Pad2)") (class "Default")
      (node (ref "R33") (pin "2") (pinfunction "2_2") (pintype "input"))
      (node (ref "U17") (pin "8") (pinfunction "RG_8") (pintype "unspecified"))
    )
    (net (code "75") (name "Net-(R34-Pad2)") (class "Default")
      (node (ref "R34") (pin "2") (pinfunction "2_2") (pintype "input"))
      (node (ref "R35") (pin "2") (pinfunction "2_2") (pintype "input"))
      (node (ref "R38") (pin "1") (pinfunction "1_1") (pintype "unspecified"))
      (node (ref "U20") (pin "5") (pinfunction "B_5") (pintype "unspecified"))
      (node (ref "U20") (pin "7") (pinfunction "B_7") (pintype "unspecified"))
    )
    (net (code "76") (name "Net-(R36-Pad1)") (class "Default")
      (node (ref "R36") (pin "1") (pinfunction "1_1") (pintype "input"))
      (node (ref "R37") (pin "1") (pinfunction "1_1") (pintype "unspecified"))
      (node (ref "R39") (pin "2") (pinfunction "2_2") (pintype "input"))
    )
    (net (code "77") (name "Net-(R41-Pad1)") (class "Default")
      (node (ref "R41") (pin "1") (pinfunction "1_1") (pintype "input"))
      (node (ref "U21") (pin "1") (pinfunction "RG_1") (pintype "unspecified"))
    )
    (net (code "78") (name "Net-(R41-Pad2)") (class "Default")
      (node (ref "R41") (pin "2") (pinfunction "2_2") (pintype "input"))
      (node (ref "U21") (pin "8") (pinfunction "RG_8") (pintype "unspecified"))
    )
    (net (code "79") (name "Net-(R42-Pad2)") (class "Default")
      (node (ref "R42") (pin "2") (pinfunction "2_2") (pintype "input"))
      (node (ref "R43") (pin "2") (pinfunction "2_2") (pintype "input"))
      (node (ref "R46") (pin "1") (pinfunction "1_1") (pintype "unspecified"))
      (node (ref "U24") (pin "5") (pinfunction "B_5") (pintype "unspecified"))
      (node (ref "U24") (pin "7") (pinfunction "B_7") (pintype "unspecified"))
    )
    (net (code "80") (name "Net-(R44-Pad1)") (class "Default")
      (node (ref "R44") (pin "1") (pinfunction "1_1") (pintype "input"))
      (node (ref "R45") (pin "1") (pinfunction "1_1") (pintype "unspecified"))
      (node (ref "R47") (pin "2") (pinfunction "2_2") (pintype "input"))
    )
    (net (code "81") (name "Net-(R49-Pad1)") (class "Default")
      (node (ref "R49") (pin "1") (pinfunction "1_1") (pintype "input"))
      (node (ref "U25") (pin "1") (pinfunction "RG_1") (pintype "unspecified"))
    )
    (net (code "82") (name "Net-(R49-Pad2)") (class "Default")
      (node (ref "R49") (pin "2") (pinfunction "2_2") (pintype "input"))
      (node (ref "U25") (pin "8") (pinfunction "RG_8") (pintype "unspecified"))
    )
    (net (code "83") (name "Net-(R50-Pad2)") (class "Default")
      (node (ref "R50") (pin "2") (pinfunction "2_2") (pintype "input"))
      (node (ref "R51") (pin "2") (pinfunction "2_2") (pintype "input"))
      (node (ref "R54") (pin "1") (pinfunction "1_1") (pintype "unspecified"))
      (node (ref "U28") (pin "5") (pinfunction "B_5") (pintype "unspecified"))
      (node (ref "U28") (pin "7") (pinfunction "B_7") (pintype "unspecified"))
    )
    (net (code "84") (name "Net-(R52-Pad1)") (class "Default")
      (node (ref "R52") (pin "1") (pinfunction "1_1") (pintype "input"))
      (node (ref "R53") (pin "1") (pinfunction "1_1") (pintype "unspecified"))
      (node (ref "R55") (pin "2") (pinfunction "2_2") (pintype "input"))
    )
    (net (code "85") (name "Net-(R57-Pad1)") (class "Default")
      (node (ref "R57") (pin "1") (pinfunction "1_1") (pintype "input"))
      (node (ref "U29") (pin "1") (pinfunction "RG_1") (pintype "unspecified"))
    )
    (net (code "86") (name "Net-(R57-Pad2)") (class "Default")
      (node (ref "R57") (pin "2") (pinfunction "2_2") (pintype "input"))
      (node (ref "U29") (pin "8") (pinfunction "RG_8") (pintype "unspecified"))
    )
    (net (code "87") (name "Net-(R58-Pad2)") (class "Default")
      (node (ref "R58") (pin "2") (pinfunction "2_2") (pintype "input"))
      (node (ref "R59") (pin "2") (pinfunction "2_2") (pintype "input"))
      (node (ref "R62") (pin "1") (pinfunction "1_1") (pintype "unspecified"))
      (node (ref "U32") (pin "5") (pinfunction "B_5") (pintype "unspecified"))
      (node (ref "U32") (pin "7") (pinfunction "B_7") (pintype "unspecified"))
    )
    (net (code "88") (name "Net-(R60-Pad1)") (class "Default")
      (node (ref "R60") (pin "1") (pinfunction "1_1") (pintype "input"))
      (node (ref "R61") (pin "1") (pinfunction "1_1") (pintype "unspecified"))
      (node (ref "R63") (pin "2") (pinfunction "2_2") (pintype "input"))
    )
    (net (code "89") (name "Net-(U2-REF)") (class "Default")
      (node (ref "C3") (pin "1") (pinfunction "1_1") (pintype "unspecified"))
      (node (ref "R21") (pin "2") (pinfunction "2_2") (pintype "unspecified"))
      (node (ref "U2") (pin "5") (pinfunction "REF_5") (pintype "unspecified"))
    )
    (net (code "90") (name "Net-(U2-VIN+)") (class "Default")
      (node (ref "C1") (pin "1") (pinfunction "1_1") (pintype "unspecified"))
      (node (ref "R14") (pin "2") (pinfunction "2_2") (pintype "unspecified"))
      (node (ref "U2") (pin "3") (pinfunction "VIN+_3") (pintype "unspecified"))
    )
    (net (code "91") (name "Net-(U2-VIN-)") (class "Default")
      (node (ref "C1") (pin "2") (pinfunction "2_2") (pintype "unspecified"))
      (node (ref "R11") (pin "2") (pinfunction "2_2") (pintype "unspecified"))
      (node (ref "U2") (pin "2") (pinfunction "VIN-_2") (pintype "unspecified"))
    )
    (net (code "92") (name "Net-(U3-REF)") (class "Default")
      (node (ref "C4") (pin "1") (pinfunction "1_1") (pintype "unspecified"))
      (node (ref "R12") (pin "2") (pinfunction "2_2") (pintype "unspecified"))
      (node (ref "U3") (pin "5") (pinfunction "REF_5") (pintype "unspecified"))
    )
    (net (code "93") (name "Net-(U3-VIN+)") (class "Default")
      (node (ref "C5") (pin "1") (pinfunction "1_1") (pintype "unspecified"))
      (node (ref "R8") (pin "2") (pinfunction "2_2") (pintype "unspecified"))
      (node (ref "U3") (pin "3") (pinfunction "VIN+_3") (pintype "unspecified"))
    )
    (net (code "94") (name "Net-(U3-VIN-)") (class "Default")
      (node (ref "C5") (pin "2") (pinfunction "2_2") (pintype "unspecified"))
      (node (ref "R9") (pin "2") (pinfunction "2_2") (pintype "unspecified"))
      (node (ref "U3") (pin "2") (pinfunction "VIN-_2") (pintype "unspecified"))
    )
    (net (code "95") (name "Net-(U4-+IN)") (class "Default")
      (node (ref "U4") (pin "1") (pinfunction "+IN_1") (pintype "unspecified"))
      (node (ref "U6") (pin "1") (pinfunction "VOUT_1") (pintype "unspecified"))
    )
    (net (code "96") (name "Net-(U4--IN)") (class "Default")
      (node (ref "R12") (pin "1") (pinfunction "1_1") (pintype "unspecified"))
      (node (ref "U4") (pin "3") (pinfunction "-IN_3") (pintype "unspecified"))
      (node (ref "U4") (pin "4") (pinfunction "OUT_4") (pintype "output"))
    )
    (net (code "97") (name "Net-(U5-+IN)") (class "Default")
      (node (ref "U5") (pin "1") (pinfunction "+IN_1") (pintype "unspecified"))
      (node (ref "U8") (pin "1") (pinfunction "VOUT_1") (pintype "unspecified"))
    )
    (net (code "98") (name "Net-(U5--IN)") (class "Default")
      (node (ref "R21") (pin "1") (pinfunction "1_1") (pintype "unspecified"))
      (node (ref "U5") (pin "3") (pinfunction "-IN_3") (pintype "unspecified"))
      (node (ref "U5") (pin "4") (pinfunction "OUT_4") (pintype "output"))
    )
    (net (code "99") (name "Net-(U9-REF)") (class "Default")
      (node (ref "C9") (pin "1") (pinfunction "1_1") (pintype "unspecified"))
      (node (ref "R24") (pin "2") (pinfunction "2_2") (pintype "unspecified"))
      (node (ref "U9") (pin "5") (pinfunction "REF_5") (pintype "unspecified"))
    )
    (net (code "100") (name "Net-(U9-VIN+)") (class "Default")
      (node (ref "C10") (pin "1") (pinfunction "1_1") (pintype "unspecified"))
      (node (ref "R18") (pin "2") (pinfunction "2_2") (pintype "unspecified"))
      (node (ref "U9") (pin "3") (pinfunction "VIN+_3") (pintype "unspecified"))
    )
    (net (code "101") (name "Net-(U9-VIN-)") (class "Default")
      (node (ref "C10") (pin "2") (pinfunction "2_2") (pintype "unspecified"))
      (node (ref "R19") (pin "2") (pinfunction "2_2") (pintype "unspecified"))
      (node (ref "U9") (pin "2") (pinfunction "VIN-_2") (pintype "unspecified"))
    )
    (net (code "102") (name "Net-(U10-+IN)") (class "Default")
      (node (ref "U10") (pin "1") (pinfunction "+IN_1") (pintype "unspecified"))
      (node (ref "U11") (pin "1") (pinfunction "VOUT_1") (pintype "unspecified"))
    )
    (net (code "103") (name "Net-(U10--IN)") (class "Default")
      (node (ref "R24") (pin "1") (pinfunction "1_1") (pintype "unspecified"))
      (node (ref "U10") (pin "3") (pinfunction "-IN_3") (pintype "unspecified"))
      (node (ref "U10") (pin "4") (pinfunction "OUT_4") (pintype "output"))
    )
    (net (code "104") (name "Net-(U13-REF)") (class "Default")
      (node (ref "C16") (pin "1") (pinfunction "1_1") (pintype "unspecified"))
      (node (ref "R32") (pin "2") (pinfunction "2_2") (pintype "unspecified"))
      (node (ref "U13") (pin "5") (pinfunction "REF_5") (pintype "unspecified"))
    )
    (net (code "105") (name "Net-(U13-VIN+)") (class "Default")
      (node (ref "C17") (pin "1") (pinfunction "1_1") (pintype "unspecified"))
      (node (ref "R29") (pin "2") (pinfunction "2_2") (pintype "unspecified"))
      (node (ref "U13") (pin "3") (pinfunction "VIN+_3") (pintype "unspecified"))
    )
    (net (code "106") (name "Net-(U13-VIN-)") (class "Default")
      (node (ref "C17") (pin "2") (pinfunction "2_2") (pintype "unspecified"))
      (node (ref "R30") (pin "2") (pinfunction "2_2") (pintype "unspecified"))
      (node (ref "U13") (pin "2") (pinfunction "VIN-_2") (pintype "unspecified"))
    )
    (net (code "107") (name "Net-(U14-+IN)") (class "Default")
      (node (ref "U14") (pin "1") (pinfunction "+IN_1") (pintype "unspecified"))
      (node (ref "U15") (pin "1") (pinfunction "VOUT_1") (pintype "unspecified"))
    )
    (net (code "108") (name "Net-(U14--IN)") (class "Default")
      (node (ref "R32") (pin "1") (pinfunction "1_1") (pintype "unspecified"))
      (node (ref "U14") (pin "3") (pinfunction "-IN_3") (pintype "unspecified"))
      (node (ref "U14") (pin "4") (pinfunction "OUT_4") (pintype "output"))
    )
    (net (code "109") (name "Net-(U17-REF)") (class "Default")
      (node (ref "C21") (pin "1") (pinfunction "1_1") (pintype "unspecified"))
      (node (ref "R40") (pin "2") (pinfunction "2_2") (pintype "unspecified"))
      (node (ref "U17") (pin "5") (pinfunction "REF_5") (pintype "unspecified"))
    )
    (net (code "110") (name "Net-(U17-VIN+)") (class "Default")
      (node (ref "C22") (pin "1") (pinfunction "1_1") (pintype "unspecified"))
      (node (ref "R37") (pin "2") (pinfunction "2_2") (pintype "unspecified"))
      (node (ref "U17") (pin "3") (pinfunction "VIN+_3") (pintype "unspecified"))
    )
    (net (code "111") (name "Net-(U17-VIN-)") (class "Default")
      (node (ref "C22") (pin "2") (pinfunction "2_2") (pintype "unspecified"))
      (node (ref "R38") (pin "2") (pinfunction "2_2") (pintype "unspecified"))
      (node (ref "U17") (pin "2") (pinfunction "VIN-_2") (pintype "unspecified"))
    )
    (net (code "112") (name "Net-(U18-+IN)") (class "Default")
      (node (ref "U18") (pin "1") (pinfunction "+IN_1") (pintype "unspecified"))
      (node (ref "U19") (pin "1") (pinfunction "VOUT_1") (pintype "unspecified"))
    )
    (net (code "113") (name "Net-(U18--IN)") (class "Default")
      (node (ref "R40") (pin "1") (pinfunction "1_1") (pintype "unspecified"))
      (node (ref "U18") (pin "3") (pinfunction "-IN_3") (pintype "unspecified"))
      (node (ref "U18") (pin "4") (pinfunction "OUT_4") (pintype "output"))
    )
    (net (code "114") (name "Net-(U21-REF)") (class "Default")
      (node (ref "C26") (pin "1") (pinfunction "1_1") (pintype "unspecified"))
      (node (ref "R48") (pin "2") (pinfunction "2_2") (pintype "unspecified"))
      (node (ref "U21") (pin "5") (pinfunction "REF_5") (pintype "unspecified"))
    )
    (net (code "115") (name "Net-(U21-VIN+)") (class "Default")
      (node (ref "C27") (pin "1") (pinfunction "1_1") (pintype "unspecified"))
      (node (ref "R45") (pin "2") (pinfunction "2_2") (pintype "unspecified"))
      (node (ref "U21") (pin "3") (pinfunction "VIN+_3") (pintype "unspecified"))
    )
    (net (code "116") (name "Net-(U21-VIN-)") (class "Default")
      (node (ref "C27") (pin "2") (pinfunction "2_2") (pintype "unspecified"))
      (node (ref "R46") (pin "2") (pinfunction "2_2") (pintype "unspecified"))
      (node (ref "U21") (pin "2") (pinfunction "VIN-_2") (pintype "unspecified"))
    )
    (net (code "117") (name "Net-(U22-+IN)") (class "Default")
      (node (ref "U22") (pin "1") (pinfunction "+IN_1") (pintype "unspecified"))
      (node (ref "U23") (pin "1") (pinfunction "VOUT_1") (pintype "unspecified"))
    )
    (net (code "118") (name "Net-(U22--IN)") (class "Default")
      (node (ref "R48") (pin "1") (pinfunction "1_1") (pintype "unspecified"))
      (node (ref "U22") (pin "3") (pinfunction "-IN_3") (pintype "unspecified"))
      (node (ref "U22") (pin "4") (pinfunction "OUT_4") (pintype "output"))
    )
    (net (code "119") (name "Net-(U25-REF)") (class "Default")
      (node (ref "C31") (pin "1") (pinfunction "1_1") (pintype "unspecified"))
      (node (ref "R56") (pin "2") (pinfunction "2_2") (pintype "unspecified"))
      (node (ref "U25") (pin "5") (pinfunction "REF_5") (pintype "unspecified"))
    )
    (net (code "120") (name "Net-(U25-VIN+)") (class "Default")
      (node (ref "C32") (pin "1") (pinfunction "1_1") (pintype "unspecified"))
      (node (ref "R53") (pin "2") (pinfunction "2_2") (pintype "unspecified"))
      (node (ref "U25") (pin "3") (pinfunction "VIN+_3") (pintype "unspecified"))
    )
    (net (code "121") (name "Net-(U25-VIN-)") (class "Default")
      (node (ref "C32") (pin "2") (pinfunction "2_2") (pintype "unspecified"))
      (node (ref "R54") (pin "2") (pinfunction "2_2") (pintype "unspecified"))
      (node (ref "U25") (pin "2") (pinfunction "VIN-_2") (pintype "unspecified"))
    )
    (net (code "122") (name "Net-(U26-+IN)") (class "Default")
      (node (ref "U26") (pin "1") (pinfunction "+IN_1") (pintype "unspecified"))
      (node (ref "U27") (pin "1") (pinfunction "VOUT_1") (pintype "unspecified"))
    )
    (net (code "123") (name "Net-(U26--IN)") (class "Default")
      (node (ref "R56") (pin "1") (pinfunction "1_1") (pintype "unspecified"))
      (node (ref "U26") (pin "3") (pinfunction "-IN_3") (pintype "unspecified"))
      (node (ref "U26") (pin "4") (pinfunction "OUT_4") (pintype "output"))
    )
    (net (code "124") (name "Net-(U29-REF)") (class "Default")
      (node (ref "C36") (pin "1") (pinfunction "1_1") (pintype "unspecified"))
      (node (ref "R64") (pin "2") (pinfunction "2_2") (pintype "unspecified"))
      (node (ref "U29") (pin "5") (pinfunction "REF_5") (pintype "unspecified"))
    )
    (net (code "125") (name "Net-(U29-VIN+)") (class "Default")
      (node (ref "C37") (pin "1") (pinfunction "1_1") (pintype "unspecified"))
      (node (ref "R61") (pin "2") (pinfunction "2_2") (pintype "unspecified"))
      (node (ref "U29") (pin "3") (pinfunction "VIN+_3") (pintype "unspecified"))
    )
    (net (code "126") (name "Net-(U29-VIN-)") (class "Default")
      (node (ref "C37") (pin "2") (pinfunction "2_2") (pintype "unspecified"))
      (node (ref "R62") (pin "2") (pinfunction "2_2") (pintype "unspecified"))
      (node (ref "U29") (pin "2") (pinfunction "VIN-_2") (pintype "unspecified"))
    )
    (net (code "127") (name "Net-(U30-+IN)") (class "Default")
      (node (ref "U30") (pin "1") (pinfunction "+IN_1") (pintype "unspecified"))
      (node (ref "U31") (pin "1") (pinfunction "VOUT_1") (pintype "unspecified"))
    )
    (net (code "128") (name "Net-(U30--IN)") (class "Default")
      (node (ref "R64") (pin "1") (pinfunction "1_1") (pintype "unspecified"))
      (node (ref "U30") (pin "3") (pinfunction "-IN_3") (pintype "unspecified"))
      (node (ref "U30") (pin "4") (pinfunction "OUT_4") (pintype "output"))
    )
    (net (code "129") (name "Net-(U34-IN+)") (class "Default")
      (node (ref "R78") (pin "1") (pinfunction "1_1") (pintype "input"))
      (node (ref "R79") (pin "2") (pinfunction "2_2") (pintype "input"))
      (node (ref "U34") (pin "3") (pinfunction "IN+_3") (pintype "unspecified"))
    )
    (net (code "130") (name "Net-(U35-RESET)") (class "Default")
      (node (ref "R73") (pin "1") (pinfunction "1_1") (pintype "input"))
      (node (ref "U35") (pin "15") (pinfunction "RESET_15") (pintype "unspecified"))
    )
    (net (code "131") (name "Net-(U35-XTAL1CLKIN)") (class "Default")
      (node (ref "C45") (pin "1") (pinfunction "1_1") (pintype "input"))
      (node (ref "U35") (pin "19") (pinfunction "XTAL1CLKIN_19") (pintype "unspecified"))
      (node (ref "U39") (pin "3") (pinfunction "3_3") (pintype "input"))
    )
    (net (code "132") (name "Net-(U35-XTAL2)") (class "Default")
      (node (ref "C57") (pin "2") (pinfunction "2_2") (pintype "input"))
      (node (ref "U35") (pin "18") (pinfunction "XTAL2_18") (pintype "unspecified"))
      (node (ref "U39") (pin "1") (pinfunction "1_1") (pintype "input"))
    )
    (net (code "133") (name "Net-(U36-BOOT)") (class "Default")
      (node (ref "C69") (pin "2") (pinfunction "2_2") (pintype "unspecified"))
      (node (ref "U36") (pin "4") (pinfunction "BOOT_4") (pintype "unspecified"))
    )
    (net (code "134") (name "Net-(U36-EN)") (class "Default")
      (node (ref "C59") (pin "2") (pinfunction "2_2") (pintype "unspecified"))
      (node (ref "C60") (pin "2") (pinfunction "2_2") (pintype "unspecified"))
      (node (ref "C61") (pin "2") (pinfunction "2_2") (pintype "unspecified"))
      (node (ref "Q3") (pin "5") (pinfunction "D_5") (pintype "unspecified"))
      (node (ref "Q3") (pin "6") (pinfunction "D_6") (pintype "unspecified"))
      (node (ref "Q3") (pin "7") (pinfunction "D_7") (pintype "unspecified"))
      (node (ref "Q3") (pin "8") (pinfunction "D_8") (pintype "unspecified"))
      (node (ref "U36") (pin "10") (pinfunction "VIN_10") (pintype "unspecified"))
      (node (ref "U36") (pin "11") (pinfunction "VIN_11") (pintype "unspecified"))
      (node (ref "U36") (pin "12") (pinfunction "VIN_12") (pintype "unspecified"))
      (node (ref "U36") (pin "9") (pinfunction "EN_9") (pintype "unspecified"))
    )
    (net (code "135") (name "Net-(U36-FB)") (class "Default")
      (node (ref "C70") (pin "2") (pinfunction "2_2") (pintype "input"))
      (node (ref "R85") (pin "1") (pinfunction "1_1") (pintype "input"))
      (node (ref "R86") (pin "2") (pinfunction "2_2") (pintype "input"))
      (node (ref "U36") (pin "7") (pinfunction "FB_7") (pintype "unspecified"))
    )
    (net (code "136") (name "Net-(U37-+IN)") (class "Default")
      (node (ref "C54") (pin "2") (pinfunction "2_2") (pintype "unspecified"))
      (node (ref "C55") (pin "2") (pinfunction "2_2") (pintype "unspecified"))
      (node (ref "R76") (pin "1") (pinfunction "1_1") (pintype "input"))
      (node (ref "U37") (pin "1") (pinfunction "+IN_1") (pintype "unspecified"))
    )
    (net (code "137") (name "Net-(U37--IN)") (class "Default")
      (node (ref "R74") (pin "1") (pinfunction "1_1") (pintype "unspecified"))
      (node (ref "U37") (pin "3") (pinfunction "-IN_3") (pintype "unspecified"))
      (node (ref "U37") (pin "4") (pinfunction "OUT_4") (pintype "output"))
    )
    (net (code "138") (name "Net-(U38-VOUT)") (class "Default")
      (node (ref "C53") (pin "1") (pinfunction "1_1") (pintype "input"))
      (node (ref "R76") (pin "2") (pinfunction "2_2") (pintype "input"))
      (node (ref "U38") (pin "4") (pinfunction "VOUT_4") (pintype "unspecified"))
    )
    (net (code "139") (name "Net-(U41-BOOT)") (class "Default")
      (node (ref "C76") (pin "1") (pinfunction "1_1") (pintype "unspecified"))
      (node (ref "U41") (pin "8") (pinfunction "BOOT_8") (pintype "unspecified"))
    )
    (net (code "140") (name "Net-(U41-COMP)") (class "Default")
      (node (ref "C83") (pin "1") (pinfunction "1_1") (pintype "input"))
      (node (ref "R91") (pin "1") (pinfunction "1_1") (pintype "input"))
      (node (ref "U41") (pin "18") (pinfunction "COMP_18") (pintype "unspecified"))
    )
    (net (code "141") (name "Net-(U41-FB)") (class "Default")
      (node (ref "R89") (pin "1") (pinfunction "1_1") (pintype "input"))
      (node (ref "R90") (pin "2") (pinfunction "2_2") (pintype "input"))
      (node (ref "U41") (pin "17") (pinfunction "FB_17") (pintype "unspecified"))
    )
    (net (code "142") (name "Net-(U41-FSW)") (class "Default")
      (node (ref "R88") (pin "2") (pinfunction "2_2") (pintype "input"))
      (node (ref "U41") (pin "3") (pinfunction "FSW_3") (pintype "unspecified"))
    )
    (net (code "143") (name "Net-(U41-ILIM)") (class "Default")
      (node (ref "R99") (pin "1") (pinfunction "1_1") (pintype "input"))
      (node (ref "U41") (pin "19") (pinfunction "ILIM_19") (pintype "unspecified"))
    )
    (net (code "144") (name "Net-(U41-SS)") (class "Default")
      (node (ref "C84") (pin "2") (pinfunction "2_2") (pintype "input"))
      (node (ref "U41") (pin "10") (pinfunction "SS_10") (pintype "unspecified"))
    )
    (net (code "145") (name "Net-(U41-VCC)") (class "Default")
      (node (ref "C77") (pin "2") (pinfunction "2_2") (pintype "input"))
      (node (ref "U41") (pin "1") (pinfunction "VCC_1") (pintype "unspecified"))
    )
    (net (code "146") (name "Net-(U42-EN)") (class "Default")
      (node (ref "R100") (pin "1") (pinfunction "1_1") (pintype "input"))
      (node (ref "U42") (pin "3") (pinfunction "EN_3") (pintype "unspecified"))
    )
    (net (code "147") (name "Net-(U43-PG)") (class "Default")
      (node (ref "R104") (pin "1") (pinfunction "1_1") (pintype "input"))
      (node (ref "U43") (pin "8") (pinfunction "PG_8") (pintype "unspecified"))
    )
    (net (code "148") (name "Net-(U43-SW)") (class "Default")
      (node (ref "L3") (pin "1") (pinfunction "1_1") (pintype "unspecified"))
      (node (ref "U43") (pin "7") (pinfunction "SW_7") (pintype "passive"))
    )
    (net (code "149") (name "Net-(U44-O1)") (class "Default")
      (node (ref "CN1") (pin "2") (pinfunction "2_2") (pintype "unspecified"))
      (node (ref "U44") (pin "16") (pinfunction "O1_16") (pintype "unspecified"))
    )
    (net (code "150") (name "Net-(U44-O2)") (class "Default")
      (node (ref "J2") (pin "2") (pinfunction "2_2") (pintype "unspecified"))
      (node (ref "U44") (pin "15") (pinfunction "O2_15") (pintype "unspecified"))
    )
    (net (code "151") (name "Net-(U44-O3)") (class "Default")
      (node (ref "J2") (pin "3") (pinfunction "3_3") (pintype "unspecified"))
      (node (ref "U44") (pin "14") (pinfunction "O3_14") (pintype "unspecified"))
    )
    (net (code "152") (name "Net-(U46-DELAY{slash}M_RST)") (class "Default")
      (node (ref "R92") (pin "2") (pinfunction "2_2") (pintype "input"))
      (node (ref "U46") (pin "3") (pinfunction "DELAY/M_RST_3") (pintype "unspecified"))
    )
    (net (code "153") (name "Net-(U48-RXD)") (class "Default")
      (node (ref "R96") (pin "2") (pinfunction "2_2") (pintype "input"))
      (node (ref "U48") (pin "3") (pinfunction "RXD_3") (pintype "unspecified"))
    )
    (net (code "154") (name "Net-(U51-CLK)") (class "Default")
      (node (ref "R105") (pin "2") (pinfunction "2_2") (pintype "input"))
      (node (ref "U51") (pin "1") (pinfunction "CLK_1") (pintype "unspecified"))
    )
    (net (code "155") (name "Net-(U51-D)") (class "Default")
      (node (ref "R106") (pin "2") (pinfunction "2_2") (pintype "input"))
      (node (ref "U51") (pin "2") (pinfunction "D_2") (pintype "unspecified"))
    )
    (net (code "156") (name "PDOWN") (class "Default")
      (node (ref "R75") (pin "1") (pinfunction "1_1") (pintype "input"))
      (node (ref "U35") (pin "14") (pinfunction "SYNCPDWN_14") (pintype "unspecified"))
      (node (ref "U49") (pin "11") (pinfunction "IO18_11") (pintype "unspecified"))
    )
    (net (code "157") (name "PG24") (class "Default")
      (node (ref "R84") (pin "1") (pinfunction "1_1") (pintype "input"))
      (node (ref "U36") (pin "5") (pinfunction "PG_5") (pintype "unspecified"))
      (node (ref "U49") (pin "26") (pinfunction "IO45_26") (pintype "unspecified"))
    )
    (net (code "158") (name "PRE") (class "Default")
      (node (ref "U51") (pin "7") (pinfunction "#PRE_7") (pintype "unspecified"))
      (node (ref "U52") (pin "4") (pinfunction "Y_4") (pintype "unspecified"))
    )
    (net (code "159") (name "RST") (class "Default")
      (node (ref "C91") (pin "2") (pinfunction "2_2") (pintype "unspecified"))
      (node (ref "Q1") (pin "6") (pinfunction "C1_6") (pintype "unspecified"))
      (node (ref "R95") (pin "1") (pinfunction "1_1") (pintype "input"))
      (node (ref "U46") (pin "6") (pinfunction "RSTn_6") (pintype "unspecified"))
      (node (ref "U49") (pin "3") (pinfunction "EN_3") (pintype "unspecified"))
    )
    (net (code "160") (name "RSTA") (class "Default")
      (node (ref "C66") (pin "2") (pinfunction "2_2") (pintype "unspecified"))
      (node (ref "R77") (pin "1") (pinfunction "1_1") (pintype "input"))
      (node (ref "U33") (pin "3") (pinfunction "RESET#_3") (pintype "unspecified"))
    )
    (net (code "161") (name "RTS") (class "Default")
      (node (ref "Q1") (pin "1") (pinfunction "E1_1") (pintype "unspecified"))
      (node (ref "Q1") (pin "5") (pinfunction "B2_5") (pintype "unspecified"))
      (node (ref "U48") (pin "14") (pinfunction "RTS#_14") (pintype "unspecified"))
    )
    (net (code "162") (name "RX2") (class "Default")
      (node (ref "U47") (pin "1") (pinfunction "R_1") (pintype "unspecified"))
      (node (ref "U49") (pin "14") (pinfunction "IO20_14") (pintype "unspecified"))
    )
    (net (code "163") (name "RXD") (class "Default")
      (node (ref "U48") (pin "2") (pinfunction "TXD_2") (pintype "unspecified"))
      (node (ref "U49") (pin "36") (pinfunction "RXD0_36") (pintype "unspecified"))
    )
    (net (code "164") (name "RXEN") (class "Default")
      (node (ref "U45") (pin "10") (pinfunction "RXEN_10") (pintype "unspecified"))
      (node (ref "U49") (pin "5") (pinfunction "IO5_5") (pintype "unspecified"))
    )
    (net (code "165") (name "SCL") (class "Default")
      (node (ref "R98") (pin "1") (pinfunction "1_1") (pintype "input"))
      (node (ref "U33") (pin "22") (pinfunction "SCL_22") (pintype "unspecified"))
      (node (ref "U49") (pin "17") (pinfunction "IO9_17") (pintype "unspecified"))
    )
    (net (code "166") (name "SCL0") (class "Default")
      (node (ref "U27") (pin "5") (pinfunction "SCL_5") (pintype "unspecified"))
      (node (ref "U33") (pin "5") (pinfunction "SC0_5") (pintype "unspecified"))
    )
    (net (code "167") (name "SCL1") (class "Default")
      (node (ref "U31") (pin "5") (pinfunction "SCL_5") (pintype "unspecified"))
      (node (ref "U33") (pin "7") (pinfunction "SC1_7") (pintype "unspecified"))
    )
    (net (code "168") (name "SCL2") (class "Default")
      (node (ref "U23") (pin "5") (pinfunction "SCL_5") (pintype "unspecified"))
      (node (ref "U33") (pin "9") (pinfunction "SC2_9") (pintype "unspecified"))
    )
    (net (code "169") (name "SCL3") (class "Default")
      (node (ref "U19") (pin "5") (pinfunction "SCL_5") (pintype "unspecified"))
      (node (ref "U33") (pin "11") (pinfunction "SC3_11") (pintype "unspecified"))
    )
    (net (code "170") (name "SCL4") (class "Default")
      (node (ref "U15") (pin "5") (pinfunction "SCL_5") (pintype "unspecified"))
      (node (ref "U33") (pin "14") (pinfunction "SC4_14") (pintype "unspecified"))
    )
    (net (code "171") (name "SCL5") (class "Default")
      (node (ref "U11") (pin "5") (pinfunction "SCL_5") (pintype "unspecified"))
      (node (ref "U33") (pin "16") (pinfunction "SC5_16") (pintype "unspecified"))
    )
    (net (code "172") (name "SCL6") (class "Default")
      (node (ref "U33") (pin "18") (pinfunction "SC6_18") (pintype "unspecified"))
      (node (ref "U6") (pin "5") (pinfunction "SCL_5") (pintype "unspecified"))
    )
    (net (code "173") (name "SCL7") (class "Default")
      (node (ref "U33") (pin "20") (pinfunction "SC7_20") (pintype "unspecified"))
      (node (ref "U8") (pin "5") (pinfunction "SCL_5") (pintype "unspecified"))
    )
    (net (code "174") (name "SDA") (class "Default")
      (node (ref "R97") (pin "1") (pinfunction "1_1") (pintype "input"))
      (node (ref "U33") (pin "23") (pinfunction "SDA_23") (pintype "unspecified"))
      (node (ref "U49") (pin "12") (pinfunction "IO8_12") (pintype "unspecified"))
    )
    (net (code "175") (name "SDA0") (class "Default")
      (node (ref "U27") (pin "4") (pinfunction "SDA_4") (pintype "unspecified"))
      (node (ref "U33") (pin "4") (pinfunction "SD0_4") (pintype "unspecified"))
    )
    (net (code "176") (name "SDA1") (class "Default")
      (node (ref "U31") (pin "4") (pinfunction "SDA_4") (pintype "unspecified"))
      (node (ref "U33") (pin "6") (pinfunction "SD1_6") (pintype "unspecified"))
    )
    (net (code "177") (name "SDA2") (class "Default")
      (node (ref "U23") (pin "4") (pinfunction "SDA_4") (pintype "unspecified"))
      (node (ref "U33") (pin "8") (pinfunction "SD2_8") (pintype "unspecified"))
    )
    (net (code "178") (name "SDA3") (class "Default")
      (node (ref "U19") (pin "4") (pinfunction "SDA_4") (pintype "unspecified"))
      (node (ref "U33") (pin "10") (pinfunction "SD3_10") (pintype "unspecified"))
    )
    (net (code "179") (name "SDA4") (class "Default")
      (node (ref "U15") (pin "4") (pinfunction "SDA_4") (pintype "unspecified"))
      (node (ref "U33") (pin "13") (pinfunction "SD4_13") (pintype "unspecified"))
    )
    (net (code "180") (name "SDA5") (class "Default")
      (node (ref "U11") (pin "4") (pinfunction "SDA_4") (pintype "unspecified"))
      (node (ref "U33") (pin "15") (pinfunction "SD5_15") (pintype "unspecified"))
    )
    (net (code "181") (name "SDA6") (class "Default")
      (node (ref "U33") (pin "17") (pinfunction "SD6_17") (pintype "unspecified"))
      (node (ref "U6") (pin "4") (pinfunction "SDA_4") (pintype "unspecified"))
    )
    (net (code "182") (name "SDA7") (class "Default")
      (node (ref "U33") (pin "19") (pinfunction "SD7_19") (pintype "unspecified"))
      (node (ref "U8") (pin "4") (pinfunction "SDA_4") (pintype "unspecified"))
    )
    (net (code "183") (name "SPI_CS") (class "Default")
      (node (ref "U35") (pin "20") (pinfunction "CS_20") (pintype "unspecified"))
      (node (ref "U49") (pin "24") (pinfunction "IO47_24") (pintype "unspecified"))
    )
    (net (code "184") (name "SPI_MISO") (class "Default")
      (node (ref "U35") (pin "22") (pinfunction "DOUT_22") (pintype "unspecified"))
      (node (ref "U45") (pin "12") (pinfunction "MISO_12") (pintype "unspecified"))
      (node (ref "U49") (pin "21") (pinfunction "IO13_21") (pintype "unspecified"))
    )
    (net (code "185") (name "SPI_MOSI") (class "Default")
      (node (ref "U35") (pin "23") (pinfunction "DIN_23") (pintype "unspecified"))
      (node (ref "U45") (pin "13") (pinfunction "MOSI_13") (pintype "unspecified"))
      (node (ref "U49") (pin "19") (pinfunction "IO11_19") (pintype "unspecified"))
    )
    (net (code "186") (name "SPI_SCK") (class "Default")
      (node (ref "U35") (pin "24") (pinfunction "SCLK_24") (pintype "unspecified"))
      (node (ref "U45") (pin "15") (pinfunction "SCK_15") (pintype "unspecified"))
      (node (ref "U49") (pin "20") (pinfunction "IO12_20") (pintype "unspecified"))
    )
    (net (code "187") (name "TX2") (class "Default")
      (node (ref "U47") (pin "4") (pinfunction "D_4") (pintype "unspecified"))
      (node (ref "U49") (pin "23") (pinfunction "IO21_23") (pintype "unspecified"))
    )
    (net (code "188") (name "TXD") (class "Default")
      (node (ref "R96") (pin "1") (pinfunction "1_1") (pintype "input"))
      (node (ref "U49") (pin "37") (pinfunction "TXD0_37") (pintype "unspecified"))
    )
    (net (code "189") (name "TXEN") (class "Default")
      (node (ref "U45") (pin "9") (pinfunction "TXEN_9") (pintype "unspecified"))
      (node (ref "U49") (pin "6") (pinfunction "IO6_6") (pintype "unspecified"))
    )
    (net (code "190") (name "VBAT") (class "Default")
      (node (ref "C74") (pin "2") (pinfunction "2_2") (pintype "unspecified"))
      (node (ref "C75") (pin "2") (pinfunction "2_2") (pintype "unspecified"))
      (node (ref "D3") (pin "1") (pinfunction "A1_1") (pintype "unspecified"))
      (node (ref "J1") (pin "2") (pinfunction "2_2") (pintype "input"))
      (node (ref "L2") (pin "1") (pinfunction "1_1") (pintype "unspecified"))
      (node (ref "R83") (pin "2") (pinfunction "2_2") (pintype "input"))
      (node (ref "U41") (pin "9") (pinfunction "VIN_9") (pintype "unspecified"))
    )
    (net (code "191") (name "VBUS") (class "Default")
      (node (ref "USB1") (pin "1") (pinfunction "VBUS_1") (pintype "unspecified"))
    )
    (net (code "192") (name "VCC") (class "Default")
      (node (ref "C58") (pin "2") (pinfunction "2_2") (pintype "unspecified"))
      (node (ref "C85") (pin "2") (pinfunction "2_2") (pintype "unspecified"))
      (node (ref "C86") (pin "2") (pinfunction "2_2") (pintype "unspecified"))
      (node (ref "C87") (pin "2") (pinfunction "2_2") (pintype "unspecified"))
      (node (ref "C88") (pin "2") (pinfunction "2_2") (pintype "unspecified"))
      (node (ref "C89") (pin "2") (pinfunction "2_2") (pintype "unspecified"))
      (node (ref "C92") (pin "2") (pinfunction "2_2") (pintype "unspecified"))
      (node (ref "C93") (pin "2") (pinfunction "2_2") (pintype "input"))
      (node (ref "C95") (pin "2") (pinfunction "2_2") (pintype "unspecified"))
      (node (ref "C96") (pin "2") (pinfunction "2_2") (pintype "unspecified"))
      (node (ref "L3") (pin "2") (pinfunction "2_2") (pintype "unspecified"))
      (node (ref "LED1") (pin "1") (pinfunction "A_1") (pintype "input"))
      (node (ref "R104") (pin "2") (pinfunction "2_2") (pintype "input"))
      (node (ref "R73") (pin "2") (pinfunction "2_2") (pintype "input"))
      (node (ref "R75") (pin "2") (pinfunction "2_2") (pintype "input"))
      (node (ref "R80") (pin "1") (pinfunction "1_1") (pintype "input"))
      (node (ref "R84") (pin "2") (pinfunction "2_2") (pintype "input"))
      (node (ref "R94") (pin "2") (pinfunction "2_2") (pintype "input"))
      (node (ref "R95") (pin "2") (pinfunction "2_2") (pintype "input"))
      (node (ref "R97") (pin "2") (pinfunction "2_2") (pintype "input"))
      (node (ref "R98") (pin "2") (pinfunction "2_2") (pintype "input"))
      (node (ref "U35") (pin "16") (pinfunction "DVDD_16") (pintype "passive"))
      (node (ref "U43") (pin "6") (pinfunction "VOS_6") (pintype "unspecified"))
      (node (ref "U45") (pin "1") (pinfunction "VCC_1") (pintype "unspecified"))
      (node (ref "U47") (pin "8") (pinfunction "VCC_8") (pintype "unspecified"))
      (node (ref "U48") (pin "16") (pinfunction "VCC_16") (pintype "unspecified"))
      (node (ref "U48") (pin "4") (pinfunction "V3_4") (pintype "unspecified"))
      (node (ref "U49") (pin "2") (pinfunction "3V3_2") (pintype "passive"))
    )
    (net (code "193") (name "VREF") (class "Default")
      (node (ref "C51") (pin "2") (pinfunction "2_2") (pintype "unspecified"))
      (node (ref "C56") (pin "1") (pinfunction "1_1") (pintype "input"))
      (node (ref "R74") (pin "2") (pinfunction "2_2") (pintype "unspecified"))
      (node (ref "U35") (pin "4") (pinfunction "VREFP_4") (pintype "unspecified"))
    )
    (net (code "194") (name "WAKE") (class "Default")
      (node (ref "U46") (pin "5") (pinfunction "WAKE_5") (pintype "unspecified"))
      (node (ref "U52") (pin "2") (pinfunction "A_2") (pintype "unspecified"))
    )
    (net (code "195") (name "unconnected-(U1-NC-Pad4)") (class "Default")
      (node (ref "U1") (pin "4") (pinfunction "NC_4") (pintype "unspecified+no_connect"))
    )
    (net (code "196") (name "unconnected-(U7-NC-Pad4)") (class "Default")
      (node (ref "U7") (pin "4") (pinfunction "NC_4") (pintype "unspecified+no_connect"))
    )
    (net (code "197") (name "unconnected-(U12-NC-Pad4)") (class "Default")
      (node (ref "U12") (pin "4") (pinfunction "NC_4") (pintype "unspecified+no_connect"))
    )
    (net (code "198") (name "unconnected-(U16-NC-Pad4)") (class "Default")
      (node (ref "U16") (pin "4") (pinfunction "NC_4") (pintype "unspecified+no_connect"))
    )
    (net (code "199") (name "unconnected-(U20-NC-Pad4)") (class "Default")
      (node (ref "U20") (pin "4") (pinfunction "NC_4") (pintype "unspecified+no_connect"))
    )
    (net (code "200") (name "unconnected-(U24-NC-Pad4)") (class "Default")
      (node (ref "U24") (pin "4") (pinfunction "NC_4") (pintype "unspecified+no_connect"))
    )
    (net (code "201") (name "unconnected-(U28-NC-Pad4)") (class "Default")
      (node (ref "U28") (pin "4") (pinfunction "NC_4") (pintype "unspecified+no_connect"))
    )
    (net (code "202") (name "unconnected-(U32-NC-Pad4)") (class "Default")
      (node (ref "U32") (pin "4") (pinfunction "NC_4") (pintype "unspecified+no_connect"))
    )
    (net (code "203") (name "unconnected-(U35-D0CLKOUT-Pad25)") (class "Default")
      (node (ref "U35") (pin "25") (pinfunction "D0CLKOUT_25") (pintype "bidirectional+no_connect"))
    )
    (net (code "204") (name "unconnected-(U35-D1-Pad26)") (class "Default")
      (node (ref "U35") (pin "26") (pinfunction "D1_26") (pintype "bidirectional+no_connect"))
    )
    (net (code "205") (name "unconnected-(U35-D2-Pad27)") (class "Default")
      (node (ref "U35") (pin "27") (pinfunction "D2_27") (pintype "bidirectional+no_connect"))
    )
    (net (code "206") (name "unconnected-(U35-D3-Pad28)") (class "Default")
      (node (ref "U35") (pin "28") (pinfunction "D3_28") (pintype "bidirectional+no_connect"))
    )
    (net (code "207") (name "unconnected-(U36-RT-Pad6)") (class "Default")
      (node (ref "U36") (pin "6") (pinfunction "RT_6") (pintype "unspecified+no_connect"))
    )
    (net (code "208") (name "unconnected-(U38-TEMP-Pad1)") (class "Default")
      (node (ref "U38") (pin "1") (pinfunction "TEMP_1") (pintype "unspecified+no_connect"))
    )
    (net (code "209") (name "unconnected-(U38-TRIM-Pad5)") (class "Default")
      (node (ref "U38") (pin "5") (pinfunction "TRIM_5") (pintype "unspecified+no_connect"))
    )
    (net (code "210") (name "unconnected-(U41-MODE-Pad13)") (class "Default")
      (node (ref "U41") (pin "13") (pinfunction "MODE_13") (pintype "unspecified+no_connect"))
    )
    (net (code "211") (name "unconnected-(U41-NC-Pad11)") (class "Default")
      (node (ref "U41") (pin "11") (pinfunction "NC_11") (pintype "unspecified+no_connect"))
    )
    (net (code "212") (name "unconnected-(U41-NC-Pad12)") (class "Default")
      (node (ref "U41") (pin "12") (pinfunction "NC_12") (pintype "unspecified+no_connect"))
    )
    (net (code "213") (name "unconnected-(U42-NC-Pad4)") (class "Default")
      (node (ref "U42") (pin "4") (pinfunction "NC_4") (pintype "unspecified+no_connect"))
    )
    (net (code "214") (name "unconnected-(U44-I4-Pad4)") (class "Default")
      (node (ref "U44") (pin "4") (pinfunction "I4_4") (pintype "unspecified"))
    )
    (net (code "215") (name "unconnected-(U44-I5-Pad5)") (class "Default")
      (node (ref "U44") (pin "5") (pinfunction "I5_5") (pintype "unspecified"))
    )
    (net (code "216") (name "unconnected-(U44-I6-Pad6)") (class "Default")
      (node (ref "U44") (pin "6") (pinfunction "I6_6") (pintype "unspecified"))
    )
    (net (code "217") (name "unconnected-(U44-I7-Pad7)") (class "Default")
      (node (ref "U44") (pin "7") (pinfunction "I7_7") (pintype "unspecified"))
    )
    (net (code "218") (name "unconnected-(U44-O4-Pad13)") (class "Default")
      (node (ref "U44") (pin "13") (pinfunction "O4_13") (pintype "unspecified"))
    )
    (net (code "219") (name "unconnected-(U44-O5-Pad12)") (class "Default")
      (node (ref "U44") (pin "12") (pinfunction "O5_12") (pintype "unspecified"))
    )
    (net (code "220") (name "unconnected-(U44-O6-Pad11)") (class "Default")
      (node (ref "U44") (pin "11") (pinfunction "O6_11") (pintype "unspecified"))
    )
    (net (code "221") (name "unconnected-(U44-O7-Pad10)") (class "Default")
      (node (ref "U44") (pin "10") (pinfunction "O7_10") (pintype "unspecified"))
    )
    (net (code "222") (name "unconnected-(U45-DIO2-Pad19)") (class "Default")
      (node (ref "U45") (pin "19") (pinfunction "DIO2_19") (pintype "unspecified"))
    )
    (net (code "223") (name "unconnected-(U45-DIO3-Pad18)") (class "Default")
      (node (ref "U45") (pin "18") (pinfunction "DIO3_18") (pintype "unspecified"))
    )
    (net (code "224") (name "unconnected-(U45-NC-Pad4)") (class "Default")
      (node (ref "U45") (pin "4") (pinfunction "NC_4") (pintype "unspecified+no_connect"))
    )
    (net (code "225") (name "unconnected-(U45-NC-Pad5)") (class "Default")
      (node (ref "U45") (pin "5") (pinfunction "NC_5") (pintype "unspecified+no_connect"))
    )
    (net (code "226") (name "unconnected-(U45-NC-Pad8)") (class "Default")
      (node (ref "U45") (pin "8") (pinfunction "NC_8") (pintype "unspecified+no_connect"))
    )
    (net (code "227") (name "unconnected-(U45-NC-Pad17)") (class "Default")
      (node (ref "U45") (pin "17") (pinfunction "NC_17") (pintype "unspecified+no_connect"))
    )
    (net (code "228") (name "unconnected-(U48-CTS#-Pad9)") (class "Default")
      (node (ref "U48") (pin "9") (pinfunction "CTS#_9") (pintype "unspecified"))
    )
    (net (code "229") (name "unconnected-(U48-DCD#-Pad12)") (class "Default")
      (node (ref "U48") (pin "12") (pinfunction "DCD#_12") (pintype "unspecified"))
    )
    (net (code "230") (name "unconnected-(U48-DSR#-Pad10)") (class "Default")
      (node (ref "U48") (pin "10") (pinfunction "DSR#_10") (pintype "unspecified"))
    )
    (net (code "231") (name "unconnected-(U48-NC.-Pad7)") (class "Default")
      (node (ref "U48") (pin "7") (pinfunction "NC._7") (pintype "unspecified+no_connect"))
    )
    (net (code "232") (name "unconnected-(U48-NC.-Pad8)") (class "Default")
      (node (ref "U48") (pin "8") (pinfunction "NC._8") (pintype "unspecified+no_connect"))
    )
    (net (code "233") (name "unconnected-(U48-R232-Pad15)") (class "Default")
      (node (ref "U48") (pin "15") (pinfunction "R232_15") (pintype "unspecified"))
    )
    (net (code "234") (name "unconnected-(U48-RI#-Pad11)") (class "Default")
      (node (ref "U48") (pin "11") (pinfunction "RI#_11") (pintype "unspecified"))
    )
    (net (code "235") (name "unconnected-(U49-IO3-Pad15)") (class "Default")
      (node (ref "U49") (pin "15") (pinfunction "IO3_15") (pintype "unspecified"))
    )
    (net (code "236") (name "unconnected-(U49-IO17-Pad10)") (class "Default")
      (node (ref "U49") (pin "10") (pinfunction "IO17_10") (pintype "unspecified"))
    )
    (net (code "237") (name "unconnected-(U49-IO35-Pad28)") (class "Default")
      (node (ref "U49") (pin "28") (pinfunction "IO35_28") (pintype "unspecified"))
    )
    (net (code "238") (name "unconnected-(U49-IO36-Pad29)") (class "Default")
      (node (ref "U49") (pin "29") (pinfunction "IO36_29") (pintype "unspecified"))
    )
    (net (code "239") (name "unconnected-(U49-IO37-Pad30)") (class "Default")
      (node (ref "U49") (pin "30") (pinfunction "IO37_30") (pintype "unspecified"))
    )
    (net (code "240") (name "unconnected-(U49-IO46-Pad16)") (class "Default")
      (node (ref "U49") (pin "16") (pinfunction "IO46_16") (pintype "unspecified"))
    )
    (net (code "241") (name "unconnected-(U49-IO48-Pad25)") (class "Default")
      (node (ref "U49") (pin "25") (pinfunction "IO48_25") (pintype "unspecified"))
    )
    (net (code "242") (name "unconnected-(U51-#Q-Pad3)") (class "Default")
      (node (ref "U51") (pin "3") (pinfunction "#Q_3") (pintype "unspecified+no_connect"))
    )
    (net (code "243") (name "unconnected-(U52-NC-Pad1)") (class "Default")
      (node (ref "U52") (pin "1") (pinfunction "NC_1") (pintype "unspecified+no_connect"))
    )
    (net (code "244") (name "unconnected-(USB1-ID-Pad4)") (class "Default")
      (node (ref "USB1") (pin "4") (pinfunction "ID_4") (pintype "unspecified+no_connect"))
    )
  )
)
